# SYSTEM_BLOCK.net
KiCad netlist of a schematic drawn in Altium Designer
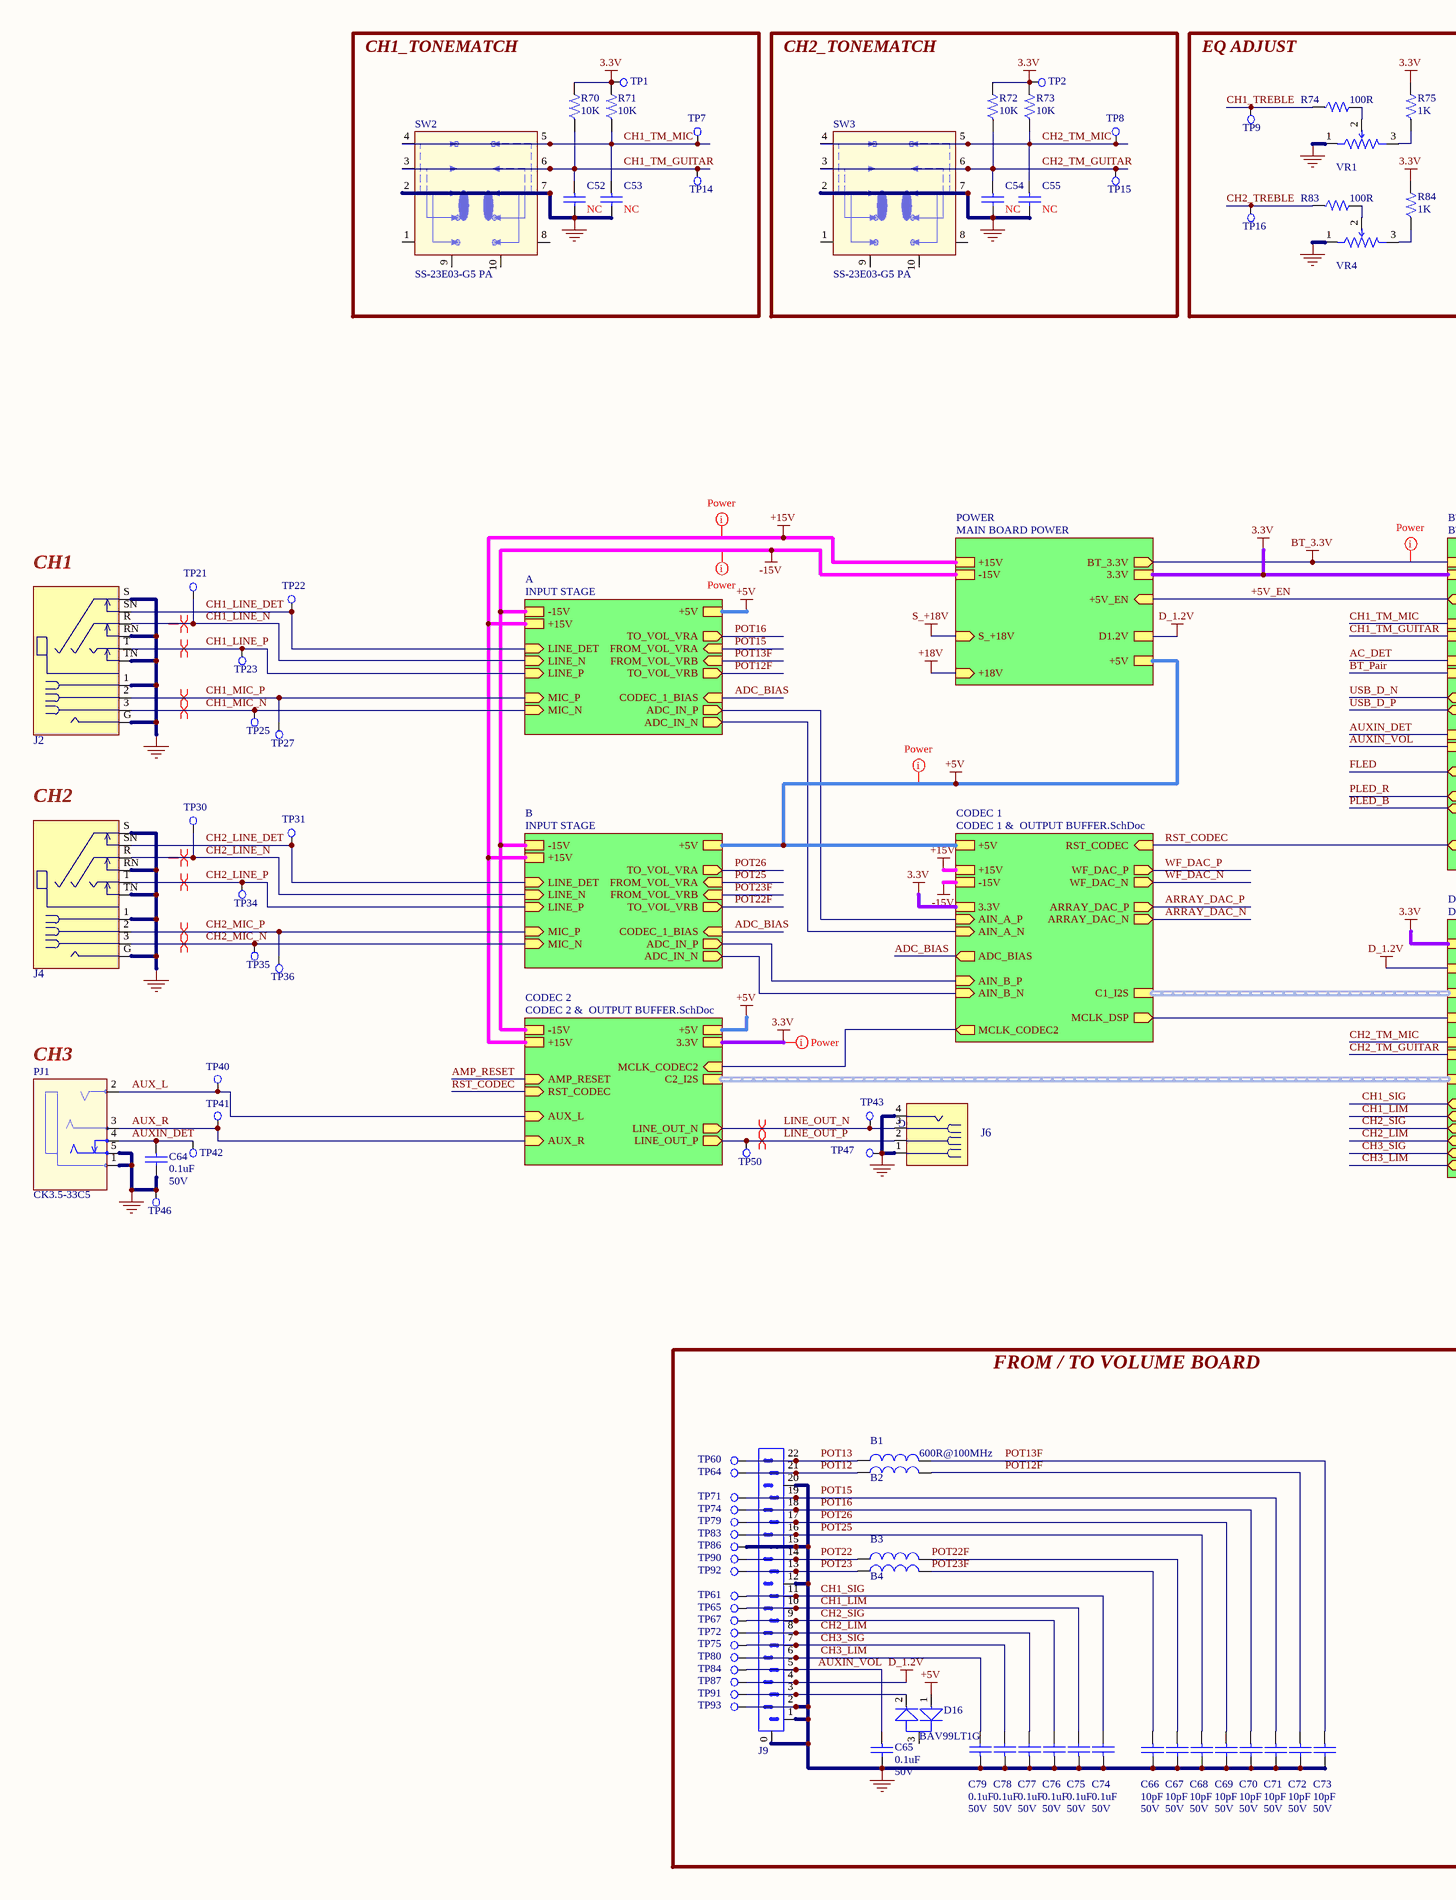
[diagram p0: SYSTEM BLOCK.SchDoc, left]
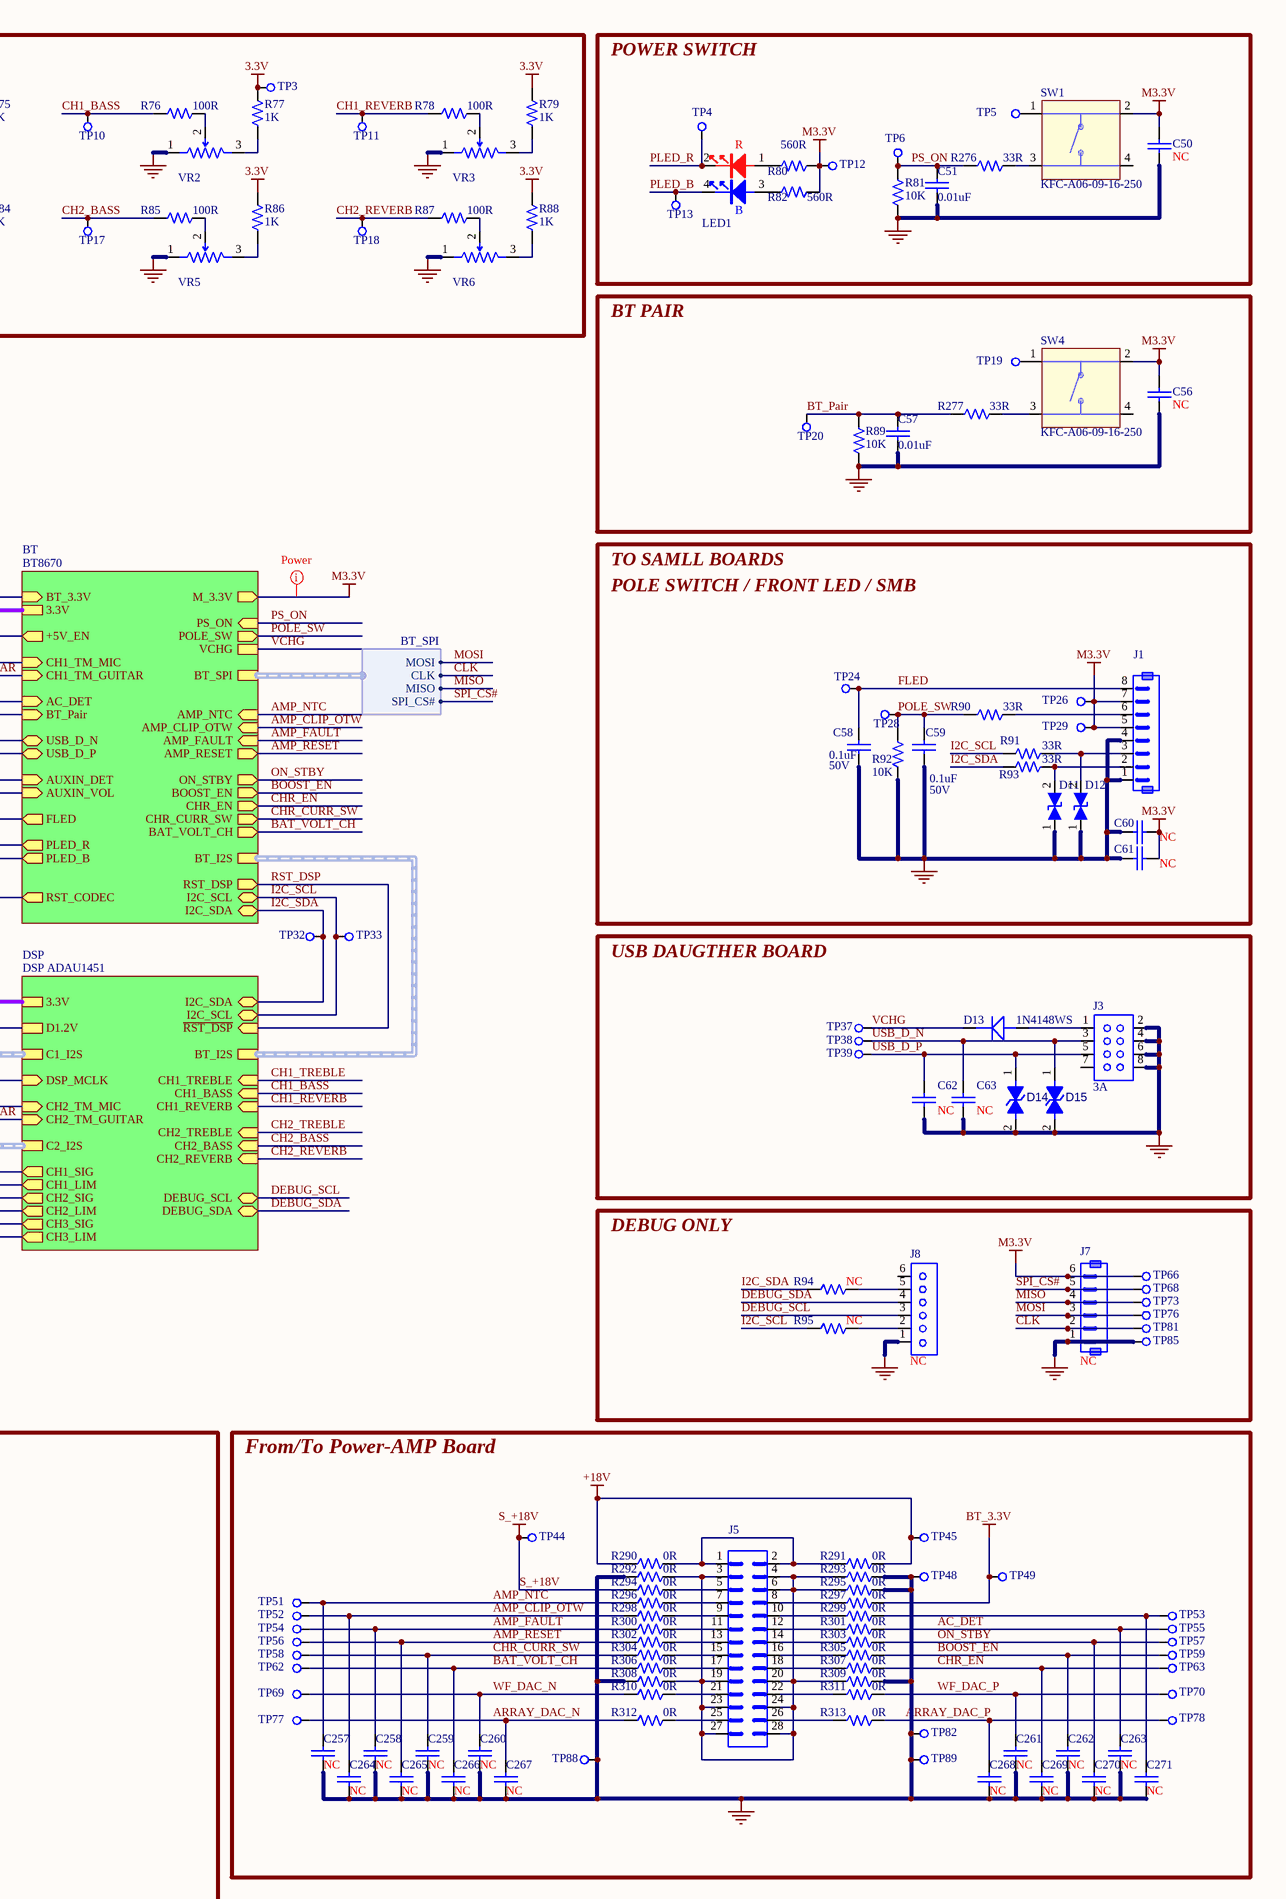
[diagram p1: SYSTEM BLOCK.SchDoc, right]

(export (version "E")
  (design (tool "Eeschema 10.0.6"))
  (components
    (comp (ref "B1")
      (value "600R@100MHz")
      (footprint "L0603-RW")
      (description "BEAD BLM18KG601SN1D 600 OHM 100M 1A L")
      (fields
        (field (name "MFG") "MURATA")
        (field (name "MFG PART") "BLM18KG601SN1D")
        (field (name "CREATE_NAME") "Nathan")
      )
      (libsource (lib "S-Inductor") (part "BEAD 0603 600R@100MHz BLM18KG601SN1D"))
    )
    (comp (ref "B2")
      (value "T710500029300")
      (footprint "L0603-RW")
      (description "BEAD BLM18KG601SN1D 600 OHM 100M 1A L")
      (fields
        (field (name "MFG") "MURATA")
        (field (name "MFG PART") "BLM18KG601SN1D")
        (field (name "CREATE_NAME") "Nathan")
      )
      (libsource (lib "S-Inductor") (part "BEAD 0603 600R@100MHz BLM18KG601SN1D"))
    )
    (comp (ref "B3")
      (value "T710500029300")
      (footprint "L0603-RW")
      (description "BEAD BLM18KG601SN1D 600 OHM 100M 1A L")
      (fields
        (field (name "MFG") "MURATA")
        (field (name "MFG PART") "BLM18KG601SN1D")
        (field (name "CREATE_NAME") "Nathan")
      )
      (libsource (lib "S-Inductor") (part "BEAD 0603 600R@100MHz BLM18KG601SN1D"))
    )
    (comp (ref "B4")
      (value "T710500029300")
      (footprint "L0603-RW")
      (description "BEAD BLM18KG601SN1D 600 OHM 100M 1A L")
      (fields
        (field (name "MFG") "MURATA")
        (field (name "MFG PART") "BLM18KG601SN1D")
        (field (name "CREATE_NAME") "Nathan")
      )
      (libsource (lib "S-Inductor") (part "BEAD 0603 600R@100MHz BLM18KG601SN1D"))
    )
    (comp (ref "C50")
      (value "NC")
      (footprint "CAPC0402-RW")
      (fields (field (name "Comment") "CAP0402 NC") (field (name "CREATE_NAME") "Tom"))
      (libsource (lib "Temporary") (part "CAP0402 NC"))
    )
    (comp (ref "C51")
      (value "0.01uF")
      (footprint "CAPC0402-RW")
      (description "CAP, CER, 0.01uF, 10%, 50V, X7R, 0402, RoHS")
      (fields
        (field (name "TOLERANCE") "10%")
        (field (name "VOLTAGE") "50V")
        (field (name "CREATE_NAME") "Evan@Deftronics")
      )
      (libsource (lib "P-Capacitors") (part "CAP0402 0.01uF 50V 10%"))
    )
    (comp (ref "C52")
      (value "NC")
      (footprint "CAPC0402-RW")
      (fields (field (name "Comment") "CAP0402 NC") (field (name "CREATE_NAME") "Tom"))
      (libsource (lib "Temporary") (part "CAP0402 NC"))
    )
    (comp (ref "C53")
      (value "NC")
      (footprint "CAPC0402-RW")
      (fields (field (name "Comment") "CAP0402 NC") (field (name "CREATE_NAME") "Tom"))
      (libsource (lib "Temporary") (part "CAP0402 NC"))
    )
    (comp (ref "C54")
      (value "NC")
      (footprint "CAPC0402-RW")
      (fields (field (name "Comment") "CAP0402 NC") (field (name "CREATE_NAME") "Tom"))
      (libsource (lib "Temporary") (part "CAP0402 NC"))
    )
    (comp (ref "C55")
      (value "NC")
      (footprint "CAPC0402-RW")
      (fields (field (name "Comment") "CAP0402 NC") (field (name "CREATE_NAME") "Tom"))
      (libsource (lib "Temporary") (part "CAP0402 NC"))
    )
    (comp (ref "C56")
      (value "NC")
      (footprint "CAPC0402-RW")
      (fields (field (name "Comment") "CAP0402 NC") (field (name "CREATE_NAME") "Tom"))
      (libsource (lib "Temporary") (part "CAP0402 NC"))
    )
    (comp (ref "C57")
      (value "0.01uF")
      (footprint "CAPC0402-RW")
      (description "CAP, CER, 0.01uF, 10%, 50V, X7R, 0402, RoHS")
      (fields
        (field (name "TOLERANCE") "10%")
        (field (name "VOLTAGE") "50V")
        (field (name "CREATE_NAME") "Evan@Deftronics")
      )
      (libsource (lib "P-Capacitors") (part "CAP0402 0.01uF 50V 10%"))
    )
    (comp (ref "C58")
      (value "0.1uF")
      (footprint "CAPC0402-RW")
      (description "CAP, CER, 0.1uF, 10%, 50V, X7R, 0402, RoHS")
      (fields
        (field (name "TOLERANCE") "10%")
        (field (name "VOLTAGE") "50V")
        (field (name "Comment") "PWL456470-1040")
        (field (name "CREATE_NAME") "TOM@Deftronics")
      )
      (libsource (lib "P-Capacitors") (part "CAP0402 0.1uF 50V 10%"))
    )
    (comp (ref "C59")
      (value "0.1uF")
      (footprint "CAPC0402-RW")
      (description "CAP, CER, 0.1uF, 10%, 50V, X7R, 0402, RoHS")
      (fields
        (field (name "TOLERANCE") "10%")
        (field (name "VOLTAGE") "50V")
        (field (name "Comment") "PWL456470-1040")
        (field (name "CREATE_NAME") "TOM@Deftronics")
      )
      (libsource (lib "P-Capacitors") (part "CAP0402 0.1uF 50V 10%"))
    )
    (comp (ref "C60")
      (value "NC")
      (footprint "CAPC0402-RW")
      (fields (field (name "Comment") "CAP0402 NC") (field (name "CREATE_NAME") "Tom"))
      (libsource (lib "Temporary") (part "CAP0402 NC"))
    )
    (comp (ref "C61")
      (value "NC")
      (footprint "CAPC0402-RW")
      (fields (field (name "Comment") "CAP0402 NC") (field (name "CREATE_NAME") "Tom"))
      (libsource (lib "Temporary") (part "CAP0402 NC"))
    )
    (comp (ref "C62")
      (value "NC")
      (footprint "CAPC0402-RW")
      (fields (field (name "Comment") "CAP0402 NC") (field (name "CREATE_NAME") "Tom"))
      (libsource (lib "Temporary") (part "CAP0402 NC"))
    )
    (comp (ref "C63")
      (value "NC")
      (footprint "CAPC0402-RW")
      (fields (field (name "Comment") "CAP0402 NC") (field (name "CREATE_NAME") "Tom"))
      (libsource (lib "Temporary") (part "CAP0402 NC"))
    )
    (comp (ref "C64")
      (value "0.1uF")
      (footprint "CAPC0402-RW")
      (description "CAP, CER, 0.1uF, 10%, 50V, X7R, 0402, RoHS")
      (fields
        (field (name "TOLERANCE") "10%")
        (field (name "VOLTAGE") "50V")
        (field (name "Comment") "PWL456470-1040")
        (field (name "CREATE_NAME") "TOM@Deftronics")
      )
      (libsource (lib "P-Capacitors") (part "CAP0402 0.1uF 50V 10%"))
    )
    (comp (ref "C65")
      (value "0.1uF")
      (footprint "CAPC0402-RW")
      (description "CAP, CER, 0.1uF, 10%, 50V, X7R, 0402, RoHS")
      (fields
        (field (name "TOLERANCE") "10%")
        (field (name "VOLTAGE") "50V")
        (field (name "Comment") "PWL456470-1040")
        (field (name "CREATE_NAME") "TOM@Deftronics")
      )
      (libsource (lib "P-Capacitors") (part "CAP0402 0.1uF 50V 10%"))
    )
    (comp (ref "C66")
      (value "10pF")
      (footprint "CAPC0402-RW")
      (description "CHIP CAP 5% 50V 0402 NPO 10pF")
      (fields
        (field (name "TOLERANCE") "5%")
        (field (name "VOLTAGE") "50V")
        (field (name "Comment") "PWL410371-1000")
        (field (name "CREATE_NAME") "TOM@Deftronics")
      )
      (libsource (lib "P-Capacitors") (part "CAP0402 10pF 50V 5%"))
    )
    (comp (ref "C67")
      (value "10pF")
      (footprint "CAPC0402-RW")
      (description "CHIP CAP 5% 50V 0402 NPO 10pF")
      (fields
        (field (name "TOLERANCE") "5%")
        (field (name "VOLTAGE") "50V")
        (field (name "Comment") "PWL410371-1000")
        (field (name "CREATE_NAME") "TOM@Deftronics")
      )
      (libsource (lib "P-Capacitors") (part "CAP0402 10pF 50V 5%"))
    )
    (comp (ref "C68")
      (value "10pF")
      (footprint "CAPC0402-RW")
      (description "CHIP CAP 5% 50V 0402 NPO 10pF")
      (fields
        (field (name "TOLERANCE") "5%")
        (field (name "VOLTAGE") "50V")
        (field (name "Comment") "PWL410371-1000")
        (field (name "CREATE_NAME") "TOM@Deftronics")
      )
      (libsource (lib "P-Capacitors") (part "CAP0402 10pF 50V 5%"))
    )
    (comp (ref "C69")
      (value "10pF")
      (footprint "CAPC0402-RW")
      (description "CHIP CAP 5% 50V 0402 NPO 10pF")
      (fields
        (field (name "TOLERANCE") "5%")
        (field (name "VOLTAGE") "50V")
        (field (name "Comment") "PWL410371-1000")
        (field (name "CREATE_NAME") "TOM@Deftronics")
      )
      (libsource (lib "P-Capacitors") (part "CAP0402 10pF 50V 5%"))
    )
    (comp (ref "C70")
      (value "10pF")
      (footprint "CAPC0402-RW")
      (description "CHIP CAP 5% 50V 0402 NPO 10pF")
      (fields
        (field (name "TOLERANCE") "5%")
        (field (name "VOLTAGE") "50V")
        (field (name "Comment") "PWL410371-1000")
        (field (name "CREATE_NAME") "TOM@Deftronics")
      )
      (libsource (lib "P-Capacitors") (part "CAP0402 10pF 50V 5%"))
    )
    (comp (ref "C71")
      (value "10pF")
      (footprint "CAPC0402-RW")
      (description "CHIP CAP 5% 50V 0402 NPO 10pF")
      (fields
        (field (name "TOLERANCE") "5%")
        (field (name "VOLTAGE") "50V")
        (field (name "Comment") "PWL410371-1000")
        (field (name "CREATE_NAME") "TOM@Deftronics")
      )
      (libsource (lib "P-Capacitors") (part "CAP0402 10pF 50V 5%"))
    )
    (comp (ref "C72")
      (value "10pF")
      (footprint "CAPC0402-RW")
      (description "CHIP CAP 5% 50V 0402 NPO 10pF")
      (fields
        (field (name "TOLERANCE") "5%")
        (field (name "VOLTAGE") "50V")
        (field (name "Comment") "PWL410371-1000")
        (field (name "CREATE_NAME") "TOM@Deftronics")
      )
      (libsource (lib "P-Capacitors") (part "CAP0402 10pF 50V 5%"))
    )
    (comp (ref "C73")
      (value "10pF")
      (footprint "CAPC0402-RW")
      (description "CHIP CAP 5% 50V 0402 NPO 10pF")
      (fields
        (field (name "TOLERANCE") "5%")
        (field (name "VOLTAGE") "50V")
        (field (name "Comment") "PWL410371-1000")
        (field (name "CREATE_NAME") "TOM@Deftronics")
      )
      (libsource (lib "P-Capacitors") (part "CAP0402 10pF 50V 5%"))
    )
    (comp (ref "C74")
      (value "0.1uF")
      (footprint "CAPC0402-RW")
      (description "CAP, CER, 0.1uF, 10%, 50V, X7R, 0402, RoHS")
      (fields
        (field (name "TOLERANCE") "10%")
        (field (name "VOLTAGE") "50V")
        (field (name "Comment") "PWL456470-1040")
        (field (name "CREATE_NAME") "TOM@Deftronics")
      )
      (libsource (lib "P-Capacitors") (part "CAP0402 0.1uF 50V 10%"))
    )
    (comp (ref "C75")
      (value "0.1uF")
      (footprint "CAPC0402-RW")
      (description "CAP, CER, 0.1uF, 10%, 50V, X7R, 0402, RoHS")
      (fields
        (field (name "TOLERANCE") "10%")
        (field (name "VOLTAGE") "50V")
        (field (name "Comment") "PWL456470-1040")
        (field (name "CREATE_NAME") "TOM@Deftronics")
      )
      (libsource (lib "P-Capacitors") (part "CAP0402 0.1uF 50V 10%"))
    )
    (comp (ref "C76")
      (value "0.1uF")
      (footprint "CAPC0402-RW")
      (description "CAP, CER, 0.1uF, 10%, 50V, X7R, 0402, RoHS")
      (fields
        (field (name "TOLERANCE") "10%")
        (field (name "VOLTAGE") "50V")
        (field (name "Comment") "PWL456470-1040")
        (field (name "CREATE_NAME") "TOM@Deftronics")
      )
      (libsource (lib "P-Capacitors") (part "CAP0402 0.1uF 50V 10%"))
    )
    (comp (ref "C77")
      (value "0.1uF")
      (footprint "CAPC0402-RW")
      (description "CAP, CER, 0.1uF, 10%, 50V, X7R, 0402, RoHS")
      (fields
        (field (name "TOLERANCE") "10%")
        (field (name "VOLTAGE") "50V")
        (field (name "Comment") "PWL456470-1040")
        (field (name "CREATE_NAME") "TOM@Deftronics")
      )
      (libsource (lib "P-Capacitors") (part "CAP0402 0.1uF 50V 10%"))
    )
    (comp (ref "C78")
      (value "0.1uF")
      (footprint "CAPC0402-RW")
      (description "CAP, CER, 0.1uF, 10%, 50V, X7R, 0402, RoHS")
      (fields
        (field (name "TOLERANCE") "10%")
        (field (name "VOLTAGE") "50V")
        (field (name "Comment") "PWL456470-1040")
        (field (name "CREATE_NAME") "TOM@Deftronics")
      )
      (libsource (lib "P-Capacitors") (part "CAP0402 0.1uF 50V 10%"))
    )
    (comp (ref "C79")
      (value "0.1uF")
      (footprint "CAPC0402-RW")
      (description "CAP, CER, 0.1uF, 10%, 50V, X7R, 0402, RoHS")
      (fields
        (field (name "TOLERANCE") "10%")
        (field (name "VOLTAGE") "50V")
        (field (name "Comment") "PWL456470-1040")
        (field (name "CREATE_NAME") "TOM@Deftronics")
      )
      (libsource (lib "P-Capacitors") (part "CAP0402 0.1uF 50V 10%"))
    )
    (comp (ref "C257")
      (value "NC")
      (footprint "CAPC0603-RW")
      (fields (field (name "Comment") "CAP0603 NC") (field (name "CREATE_NAME") "Tom"))
      (libsource (lib "Temporary") (part "CAP0603 NC"))
    )
    (comp (ref "C258")
      (value "NC")
      (footprint "CAPC0603-RW")
      (fields (field (name "Comment") "CAP0603 NC") (field (name "CREATE_NAME") "Tom"))
      (libsource (lib "Temporary") (part "CAP0603 NC"))
    )
    (comp (ref "C259")
      (value "NC")
      (footprint "CAPC0603-RW")
      (fields (field (name "Comment") "CAP0603 NC") (field (name "CREATE_NAME") "Tom"))
      (libsource (lib "Temporary") (part "CAP0603 NC"))
    )
    (comp (ref "C260")
      (value "NC")
      (footprint "CAPC0603-RW")
      (fields (field (name "Comment") "CAP0603 NC") (field (name "CREATE_NAME") "Tom"))
      (libsource (lib "Temporary") (part "CAP0603 NC"))
    )
    (comp (ref "C261")
      (value "NC")
      (footprint "CAPC0603-RW")
      (fields (field (name "Comment") "CAP0603 NC") (field (name "CREATE_NAME") "Tom"))
      (libsource (lib "Temporary") (part "CAP0603 NC"))
    )
    (comp (ref "C262")
      (value "NC")
      (footprint "CAPC0603-RW")
      (fields (field (name "Comment") "CAP0603 NC") (field (name "CREATE_NAME") "Tom"))
      (libsource (lib "Temporary") (part "CAP0603 NC"))
    )
    (comp (ref "C263")
      (value "NC")
      (footprint "CAPC0603-RW")
      (fields (field (name "Comment") "CAP0603 NC") (field (name "CREATE_NAME") "Tom"))
      (libsource (lib "Temporary") (part "CAP0603 NC"))
    )
    (comp (ref "C264")
      (value "NC")
      (footprint "CAPC0603-RW")
      (fields (field (name "Comment") "CAP0603 NC") (field (name "CREATE_NAME") "Tom"))
      (libsource (lib "Temporary") (part "CAP0603 NC"))
    )
    (comp (ref "C265")
      (value "NC")
      (footprint "CAPC0603-RW")
      (fields (field (name "Comment") "CAP0603 NC") (field (name "CREATE_NAME") "Tom"))
      (libsource (lib "Temporary") (part "CAP0603 NC"))
    )
    (comp (ref "C266")
      (value "NC")
      (footprint "CAPC0603-RW")
      (fields (field (name "Comment") "CAP0603 NC") (field (name "CREATE_NAME") "Tom"))
      (libsource (lib "Temporary") (part "CAP0603 NC"))
    )
    (comp (ref "C267")
      (value "NC")
      (footprint "CAPC0603-RW")
      (fields (field (name "Comment") "CAP0603 NC") (field (name "CREATE_NAME") "Tom"))
      (libsource (lib "Temporary") (part "CAP0603 NC"))
    )
    (comp (ref "C268")
      (value "NC")
      (footprint "CAPC0603-RW")
      (fields (field (name "Comment") "CAP0603 NC") (field (name "CREATE_NAME") "Tom"))
      (libsource (lib "Temporary") (part "CAP0603 NC"))
    )
    (comp (ref "C269")
      (value "NC")
      (footprint "CAPC0603-RW")
      (fields (field (name "Comment") "CAP0603 NC") (field (name "CREATE_NAME") "Tom"))
      (libsource (lib "Temporary") (part "CAP0603 NC"))
    )
    (comp (ref "C270")
      (value "NC")
      (footprint "CAPC0603-RW")
      (fields (field (name "Comment") "CAP0603 NC") (field (name "CREATE_NAME") "Tom"))
      (libsource (lib "Temporary") (part "CAP0603 NC"))
    )
    (comp (ref "C271")
      (value "NC")
      (footprint "CAPC0603-RW")
      (fields (field (name "Comment") "CAP0603 NC") (field (name "CREATE_NAME") "Tom"))
      (libsource (lib "Temporary") (part "CAP0603 NC"))
    )
    (comp (ref "D11")
      (value "T710500020400")
      (footprint "VAR-0402")
      (description "VR AVRM1005C120MTAAB TDK K")
      (fields
        (field (name "MFG") "TDK")
        (field (name "MFG PART") "AVRM1005C120MTAAB")
        (field (name "CREAT NAME") "QCD")
      )
      (libsource (lib "R-Semiconductors") (part "AVRM1005C120MTAAB"))
    )
    (comp (ref "D12")
      (value "T710500020400")
      (footprint "VAR-0402")
      (description "VR AVRM1005C120MTAAB TDK K")
      (fields
        (field (name "MFG") "TDK")
        (field (name "MFG PART") "AVRM1005C120MTAAB")
        (field (name "CREAT NAME") "QCD")
      )
      (libsource (lib "R-Semiconductors") (part "AVRM1005C120MTAAB"))
    )
    (comp (ref "D13")
      (value "RCD114148-0020")
      (footprint "SOD-323")
      (description "DIODE SW 1N4148 VF=0.7V SOD-323")
      (fields
        (field (name "MFG") "TW SEMICONDUCTOR")
        (field (name "VOLTAGE") "100V")
        (field (name "MFG PART") "1N4148WS")
      )
      (libsource (lib "R-Semiconductors") (part "1N4148WS"))
    )
    (comp (ref "D14")
      (value "T593000120100")
      (footprint "SOD882-ESD")
      (description "TVS 5V L06ESDU5V0CE SMD LITEON L")
      (fields
        (field (name "MFG") "LITEON")
        (field (name "MFG PART") "L06ESDU5V0CE2")
        (field (name "CREATE_NAME") "Tom")
      )
      (libsource (lib "R-Semiconductors") (part "L06ESDU5V0CE2"))
    )
    (comp (ref "D15")
      (value "T593000120100")
      (footprint "SOD882-ESD")
      (description "TVS 5V L06ESDU5V0CE SMD LITEON L")
      (fields
        (field (name "MFG") "LITEON")
        (field (name "MFG PART") "L06ESDU5V0CE2")
        (field (name "CREATE_NAME") "Tom")
      )
      (libsource (lib "R-Semiconductors") (part "L06ESDU5V0CE2"))
    )
    (comp (ref "D16")
      (value "RCD100099-0010")
      (footprint "SOT23-132-RW")
      (description "SWITC 70V 215MA BAV99LT1G ON SE G")
      (fields
        (field (name "MFG") "ON SEMI")
        (field (name "MFG PART") "BAV99LT1G")
        (field (name "VOLTAGE") "100V")
      )
      (libsource (lib "R-Semiconductors") (part "BAV99LT1G"))
    )
    (comp (ref "J1")
      (value "T690300162000")
      (footprint "CONN 8P PH=1.5mm ST SMT_ZH-8AT-JK")
      (description "SMT CONNECTOR 8PIN P:1.5MM 90 K")
      (fields
        (field (name "MFG") "金佳")
        (field (name "MFG PART") "ZH-8AT-JK")
        (field (name "CREATE_NAME") "Nathan")
      )
      (libsource (lib "C-Connector") (part "CONN 8P PH=1.5mm ST SMT_ZH-8AT-JK"))
    )
    (comp (ref "J2")
      (value "T710200010000")
      (footprint "CONN XLR COMBO RCJ9FI-V-0")
      (description "COMBO JACK RCJ9FI-V-0 REAN K")
      (fields
        (field (name "MFG") "REAN")
        (field (name "MFG PART") "RCJ9FI-V-0")
        (field (name "CREATE_NAME") "Nathan")
      )
      (libsource (lib "C-Connector") (part "CONN XLR COMBO RCJ9FI-V-0"))
    )
    (comp (ref "J3")
      (value "USB DAUGHTER BOARD")
      (footprint "USB DAUGHTER BOARD")
      (fields (field (name "CURRENT") "3A"))
      (libsource (lib "Yetta_Lib") (part "USB DAUGHTER BOARD"))
    )
    (comp (ref "J4")
      (value "T710200010000")
      (footprint "CONN XLR COMBO RCJ9FI-V-0")
      (description "COMBO JACK RCJ9FI-V-0 REAN K")
      (fields
        (field (name "MFG") "REAN")
        (field (name "MFG PART") "RCJ9FI-V-0")
        (field (name "CREATE_NAME") "Nathan")
      )
      (libsource (lib "C-Connector") (part "CONN XLR COMBO RCJ9FI-V-0"))
    )
    (comp (ref "J5")
      (value "T690300164900")
      (footprint "HOUSING 28P 2X14 PH=2.54mm ST SMT 2.54Y-2X14SW-10.6R")
      (description "CONNECTOR 2X14PIN P:2.54 90 H:10.6 K")
      (fields
        (field (name "MFG") "JIN JIA")
        (field (name "MFG PART") "2.54Y-2X14SW-10.6R")
        (field (name "CREATE_NAME") "Nathan")
      )
      (libsource (lib "C-Connector") (part "HOUSING 28P 2X14 PH=2.54mm ST SMT 2.54Y-2X14SW-10.6R"))
    )
    (comp (ref "J6")
      (value "T710200009900")
      (footprint "CONN XLR 3P NC3MAV-0")
      (description "3 POLE MALE XLR RECEPTACLE K")
      (fields
        (field (name "MFG") "NEUTRIK")
        (field (name "MFG PART") "NC3MAV-0")
        (field (name "CREATE_NAME") "Nathan")
      )
      (libsource (lib "C-Connector") (part "CONN XLR 3P NC3MAV-0"))
    )
    (comp (ref "J7")
      (value "NC")
      (footprint "CONN 6P PH=1.5mm ST SMT ZH-6AT-JK")
      (description "CHIP CONNECTOR 6PIN P:1.5MM 90 G")
      (fields
        (field (name "MFG") "金佳")
        (field (name "MFG PART") "ZH-6AT-JK")
        (field (name "CREATE_NAME") "Nathan")
      )
      (libsource (lib "C-Connector") (part "CONN 6P PH=1.5mm ST SMT ZH-6AT-JK"))
    )
    (comp (ref "J8")
      (value "NC")
      (footprint "CONN 6P PH=2.0MM ST_PH-6A-CS")
      (description "CONNECTOR 6IN 2.0MM DIP 180 K")
      (fields
        (field (name "MFG") "金佳电子")
        (field (name "MFG PART") "PH-6A-CS")
        (field (name "CREATE_NAME") "Nathan")
      )
      (libsource (lib "C-Connector") (part "CONN 6P PH=2.0MM ST_PH-6A-CS"))
    )
    (comp (ref "J9")
      (value "T690300162900")
      (footprint "CONN FFC 22P PH=0.5MM SMT ST 0.5S-4-22PTFAR")
      (description "FFC CONNECTOR 22P 0.5MM GOLD PLATED L")
      (fields
        (field (name "MFG") "金佳")
        (field (name "MFG PART") "0.5S-4-22PTFAR")
        (field (name "CREATE_NAME") "Nathan")
      )
      (libsource (lib "C-Connector") (part "CONN FFC 22P 2X11 PH=0.5MM SMT ST 0.5S-4-22PTFAR"))
    )
    (comp (ref "LED1")
      (value "KCD260004-0010")
      (footprint "SMTLED2.0*1.25-RGB")
      (description "SMD LED 2.0x1.25mm  MS-PTB2012CURSBAC   RED/BLUE")
      (fields
        (field (name "MFG PART") "MS-PTB2012CURSGAC  RED/BLUE")
        (field (name "MFG") "MASON")
        (field (name "CREATE_NAME") "Evan@Deftronics")
      )
      (libsource (lib "K-LED-FUSE") (part "MS-PTB2012CURSGAC_RED/BLUE"))
    )
    (comp (ref "PJ1")
      (value "T710200010500")
      (footprint "Phone Jack CK3.5-33C5")
      (description "EARPHONE JACK K")
      (fields
        (field (name "MFG") "JINJIA")
        (field (name "MFG PART") "CK3.5-33C5")
        (field (name "CREATE_NAME") "Nathan")
      )
      (libsource (lib "C-Connector") (part "PHONE JACK 3.5mm CK3.5-33C5"))
    )
    (comp (ref "R70")
      (value "10K")
      (footprint "0402-RW")
      (description "CHIP RES 10K OHM 1/16W 1% 0402")
      (fields (field (name "MFG") "WALSIN") (field (name "Comment") "QCF161240-1002"))
      (libsource (lib "Q-Resistors") (part "RES0402 1/16W 1% 10K OHM"))
    )
    (comp (ref "R71")
      (value "10K")
      (footprint "0402-RW")
      (description "CHIP RES 10K OHM 1/16W 1% 0402")
      (fields (field (name "MFG") "WALSIN") (field (name "Comment") "QCF161240-1002"))
      (libsource (lib "Q-Resistors") (part "RES0402 1/16W 1% 10K OHM"))
    )
    (comp (ref "R72")
      (value "10K")
      (footprint "0402-RW")
      (description "CHIP RES 10K OHM 1/16W 1% 0402")
      (fields (field (name "MFG") "WALSIN") (field (name "Comment") "QCF161240-1002"))
      (libsource (lib "Q-Resistors") (part "RES0402 1/16W 1% 10K OHM"))
    )
    (comp (ref "R73")
      (value "10K")
      (footprint "0402-RW")
      (description "CHIP RES 10K OHM 1/16W 1% 0402")
      (fields (field (name "MFG") "WALSIN") (field (name "Comment") "QCF161240-1002"))
      (libsource (lib "Q-Resistors") (part "RES0402 1/16W 1% 10K OHM"))
    )
    (comp (ref "R74")
      (value "100R")
      (footprint "0402-RW")
      (description "CHIP RES 100 OHM 1/16W 1% 0402")
      (fields (field (name "MFG") "WALSIN") (field (name "Comment") "QCF161240-1000"))
      (libsource (lib "Q-Resistors") (part "RES0402 1/16W 1% 100 OHM"))
    )
    (comp (ref "R75")
      (value "1K")
      (footprint "0402-RW")
      (description "CHIP RES 1K OHM 1/16W 1% 0402")
      (fields (field (name "MFG") "WALSIN") (field (name "Comment") "QCF161240-1001"))
      (libsource (lib "Q-Resistors") (part "RES0402 1/16W 1% 1K OHM"))
    )
    (comp (ref "R76")
      (value "100R")
      (footprint "0402-RW")
      (description "CHIP RES 100 OHM 1/16W 1% 0402")
      (fields (field (name "MFG") "WALSIN") (field (name "Comment") "QCF161240-1000"))
      (libsource (lib "Q-Resistors") (part "RES0402 1/16W 1% 100 OHM"))
    )
    (comp (ref "R77")
      (value "1K")
      (footprint "0402-RW")
      (description "CHIP RES 1K OHM 1/16W 1% 0402")
      (fields (field (name "MFG") "WALSIN") (field (name "Comment") "QCF161240-1001"))
      (libsource (lib "Q-Resistors") (part "RES0402 1/16W 1% 1K OHM"))
    )
    (comp (ref "R78")
      (value "100R")
      (footprint "0402-RW")
      (description "CHIP RES 100 OHM 1/16W 1% 0402")
      (fields (field (name "MFG") "WALSIN") (field (name "Comment") "QCF161240-1000"))
      (libsource (lib "Q-Resistors") (part "RES0402 1/16W 1% 100 OHM"))
    )
    (comp (ref "R79")
      (value "1K")
      (footprint "0402-RW")
      (description "CHIP RES 1K OHM 1/16W 1% 0402")
      (fields (field (name "MFG") "WALSIN") (field (name "Comment") "QCF161240-1001"))
      (libsource (lib "Q-Resistors") (part "RES0402 1/16W 1% 1K OHM"))
    )
    (comp (ref "R80")
      (value "560R")
      (footprint "0603-RW")
      (description "GP CHIP RES. 560 OHM 1/10W 1% 0603")
      (fields (field (name "Comment") "QCF011030-5600"))
      (libsource (lib "Q-Resistors") (part "RES0603 1/10W 1% 560 OHM"))
    )
    (comp (ref "R81")
      (value "10K")
      (footprint "0402-RW")
      (description "CHIP RES 10K OHM 1/16W 1% 0402")
      (fields (field (name "MFG") "WALSIN") (field (name "Comment") "QCF161240-1002"))
      (libsource (lib "Q-Resistors") (part "RES0402 1/16W 1% 10K OHM"))
    )
    (comp (ref "R82")
      (value "560R")
      (footprint "0603-RW")
      (description "GP CHIP RES. 560 OHM 1/10W 1% 0603")
      (fields (field (name "Comment") "QCF011030-5600"))
      (libsource (lib "Q-Resistors") (part "RES0603 1/10W 1% 560 OHM"))
    )
    (comp (ref "R83")
      (value "100R")
      (footprint "0402-RW")
      (description "CHIP RES 100 OHM 1/16W 1% 0402")
      (fields (field (name "MFG") "WALSIN") (field (name "Comment") "QCF161240-1000"))
      (libsource (lib "Q-Resistors") (part "RES0402 1/16W 1% 100 OHM"))
    )
    (comp (ref "R84")
      (value "1K")
      (footprint "0402-RW")
      (description "CHIP RES 1K OHM 1/16W 1% 0402")
      (fields (field (name "MFG") "WALSIN") (field (name "Comment") "QCF161240-1001"))
      (libsource (lib "Q-Resistors") (part "RES0402 1/16W 1% 1K OHM"))
    )
    (comp (ref "R85")
      (value "100R")
      (footprint "0402-RW")
      (description "CHIP RES 100 OHM 1/16W 1% 0402")
      (fields (field (name "MFG") "WALSIN") (field (name "Comment") "QCF161240-1000"))
      (libsource (lib "Q-Resistors") (part "RES0402 1/16W 1% 100 OHM"))
    )
    (comp (ref "R86")
      (value "1K")
      (footprint "0402-RW")
      (description "CHIP RES 1K OHM 1/16W 1% 0402")
      (fields (field (name "MFG") "WALSIN") (field (name "Comment") "QCF161240-1001"))
      (libsource (lib "Q-Resistors") (part "RES0402 1/16W 1% 1K OHM"))
    )
    (comp (ref "R87")
      (value "100R")
      (footprint "0402-RW")
      (description "CHIP RES 100 OHM 1/16W 1% 0402")
      (fields (field (name "MFG") "WALSIN") (field (name "Comment") "QCF161240-1000"))
      (libsource (lib "Q-Resistors") (part "RES0402 1/16W 1% 100 OHM"))
    )
    (comp (ref "R88")
      (value "1K")
      (footprint "0402-RW")
      (description "CHIP RES 1K OHM 1/16W 1% 0402")
      (fields (field (name "MFG") "WALSIN") (field (name "Comment") "QCF161240-1001"))
      (libsource (lib "Q-Resistors") (part "RES0402 1/16W 1% 1K OHM"))
    )
    (comp (ref "R89")
      (value "10K")
      (footprint "0402-RW")
      (description "CHIP RES 10K OHM 1/16W 1% 0402")
      (fields (field (name "MFG") "WALSIN") (field (name "Comment") "QCF161240-1002"))
      (libsource (lib "Q-Resistors") (part "RES0402 1/16W 1% 10K OHM"))
    )
    (comp (ref "R90")
      (value "33R")
      (footprint "0402-RW")
      (description "CHIP RES 33 OHM 1/16W 1% 0402")
      (fields (field (name "POWER") "1/16W") (field (name "MFG") "WALSIN"))
      (libsource (lib "Q-Resistors") (part "RES0402 1/16W 1% 33 OHM"))
    )
    (comp (ref "R91")
      (value "33R")
      (footprint "0402-RW")
      (description "CHIP RES 33 OHM 1/16W 1% 0402")
      (fields (field (name "POWER") "1/16W") (field (name "MFG") "WALSIN"))
      (libsource (lib "Q-Resistors") (part "RES0402 1/16W 1% 33 OHM"))
    )
    (comp (ref "R92")
      (value "10K")
      (footprint "0402-RW")
      (description "CHIP RES 10K OHM 1/16W 1% 0402")
      (fields (field (name "POWER") "1/16W") (field (name "MFG") "WALSIN"))
      (libsource (lib "Q-Resistors") (part "RES0402 1/16W 1% 10K OHM"))
    )
    (comp (ref "R93")
      (value "33R")
      (footprint "0402-RW")
      (description "CHIP RES 33 OHM 1/16W 1% 0402")
      (fields (field (name "POWER") "1/16W") (field (name "MFG") "WALSIN"))
      (libsource (lib "Q-Resistors") (part "RES0402 1/16W 1% 33 OHM"))
    )
    (comp (ref "R94")
      (value "NC")
      (footprint "0603-RW")
      (fields (field (name "Comment") "RES0603 NC") (field (name "CREATE_NAME") "Tom"))
      (libsource (lib "Temporary") (part "RES0603 NC"))
    )
    (comp (ref "R95")
      (value "NC")
      (footprint "0603-RW")
      (fields (field (name "Comment") "RES0603 NC") (field (name "CREATE_NAME") "Tom"))
      (libsource (lib "Temporary") (part "RES0603 NC"))
    )
    (comp (ref "R276")
      (value "33R")
      (footprint "0402-RW")
      (description "CHIP RES 33 OHM 1/16W 1% 0402")
      (fields (field (name "POWER") "1/16W") (field (name "MFG") "WALSIN"))
      (libsource (lib "Q-Resistors") (part "RES0402 1/16W 1% 33 OHM"))
    )
    (comp (ref "R277")
      (value "33R")
      (footprint "0402-RW")
      (description "CHIP RES 33 OHM 1/16W 1% 0402")
      (fields (field (name "POWER") "1/16W") (field (name "MFG") "WALSIN"))
      (libsource (lib "Q-Resistors") (part "RES0402 1/16W 1% 33 OHM"))
    )
    (comp (ref "R290")
      (value "0R")
      (footprint "0603-RW")
      (description "GP CHIP RES. 0 OHM 1/10W 5% 0603")
      (fields (field (name "POWER") "1/10W") (field (name "Comment") "QCF015030-0000"))
      (libsource (lib "Q-Resistors") (part "RES0603 1/10W 5% 0 OHM"))
    )
    (comp (ref "R291")
      (value "0R")
      (footprint "0603-RW")
      (description "GP CHIP RES. 0 OHM 1/10W 5% 0603")
      (fields (field (name "POWER") "1/10W") (field (name "Comment") "QCF015030-0000"))
      (libsource (lib "Q-Resistors") (part "RES0603 1/10W 5% 0 OHM"))
    )
    (comp (ref "R292")
      (value "0R")
      (footprint "0603-RW")
      (description "GP CHIP RES. 0 OHM 1/10W 5% 0603")
      (fields (field (name "POWER") "1/10W") (field (name "Comment") "QCF015030-0000"))
      (libsource (lib "Q-Resistors") (part "RES0603 1/10W 5% 0 OHM"))
    )
    (comp (ref "R293")
      (value "0R")
      (footprint "0603-RW")
      (description "GP CHIP RES. 0 OHM 1/10W 5% 0603")
      (fields (field (name "POWER") "1/10W") (field (name "Comment") "QCF015030-0000"))
      (libsource (lib "Q-Resistors") (part "RES0603 1/10W 5% 0 OHM"))
    )
    (comp (ref "R294")
      (value "0R")
      (footprint "0603-RW")
      (description "GP CHIP RES. 0 OHM 1/10W 5% 0603")
      (fields (field (name "POWER") "1/10W") (field (name "Comment") "QCF015030-0000"))
      (libsource (lib "Q-Resistors") (part "RES0603 1/10W 5% 0 OHM"))
    )
    (comp (ref "R295")
      (value "0R")
      (footprint "0603-RW")
      (description "GP CHIP RES. 0 OHM 1/10W 5% 0603")
      (fields (field (name "POWER") "1/10W") (field (name "Comment") "QCF015030-0000"))
      (libsource (lib "Q-Resistors") (part "RES0603 1/10W 5% 0 OHM"))
    )
    (comp (ref "R296")
      (value "0R")
      (footprint "0603-RW")
      (description "GP CHIP RES. 0 OHM 1/10W 5% 0603")
      (fields (field (name "POWER") "1/10W") (field (name "Comment") "QCF015030-0000"))
      (libsource (lib "Q-Resistors") (part "RES0603 1/10W 5% 0 OHM"))
    )
    (comp (ref "R297")
      (value "0R")
      (footprint "0603-RW")
      (description "GP CHIP RES. 0 OHM 1/10W 5% 0603")
      (fields (field (name "POWER") "1/10W") (field (name "Comment") "QCF015030-0000"))
      (libsource (lib "Q-Resistors") (part "RES0603 1/10W 5% 0 OHM"))
    )
    (comp (ref "R298")
      (value "0R")
      (footprint "0603-RW")
      (description "GP CHIP RES. 0 OHM 1/10W 5% 0603")
      (fields (field (name "POWER") "1/10W") (field (name "Comment") "QCF015030-0000"))
      (libsource (lib "Q-Resistors") (part "RES0603 1/10W 5% 0 OHM"))
    )
    (comp (ref "R299")
      (value "0R")
      (footprint "0603-RW")
      (description "GP CHIP RES. 0 OHM 1/10W 5% 0603")
      (fields (field (name "POWER") "1/10W") (field (name "Comment") "QCF015030-0000"))
      (libsource (lib "Q-Resistors") (part "RES0603 1/10W 5% 0 OHM"))
    )
    (comp (ref "R300")
      (value "0R")
      (footprint "0603-RW")
      (description "GP CHIP RES. 0 OHM 1/10W 5% 0603")
      (fields (field (name "POWER") "1/10W") (field (name "Comment") "QCF015030-0000"))
      (libsource (lib "Q-Resistors") (part "RES0603 1/10W 5% 0 OHM"))
    )
    (comp (ref "R301")
      (value "0R")
      (footprint "0603-RW")
      (description "GP CHIP RES. 0 OHM 1/10W 5% 0603")
      (fields (field (name "POWER") "1/10W") (field (name "Comment") "QCF015030-0000"))
      (libsource (lib "Q-Resistors") (part "RES0603 1/10W 5% 0 OHM"))
    )
    (comp (ref "R302")
      (value "0R")
      (footprint "0603-RW")
      (description "GP CHIP RES. 0 OHM 1/10W 5% 0603")
      (fields (field (name "POWER") "1/10W") (field (name "Comment") "QCF015030-0000"))
      (libsource (lib "Q-Resistors") (part "RES0603 1/10W 5% 0 OHM"))
    )
    (comp (ref "R303")
      (value "0R")
      (footprint "0603-RW")
      (description "GP CHIP RES. 0 OHM 1/10W 5% 0603")
      (fields (field (name "POWER") "1/10W") (field (name "Comment") "QCF015030-0000"))
      (libsource (lib "Q-Resistors") (part "RES0603 1/10W 5% 0 OHM"))
    )
    (comp (ref "R304")
      (value "0R")
      (footprint "0603-RW")
      (description "GP CHIP RES. 0 OHM 1/10W 5% 0603")
      (fields (field (name "POWER") "1/10W") (field (name "Comment") "QCF015030-0000"))
      (libsource (lib "Q-Resistors") (part "RES0603 1/10W 5% 0 OHM"))
    )
    (comp (ref "R305")
      (value "0R")
      (footprint "0603-RW")
      (description "GP CHIP RES. 0 OHM 1/10W 5% 0603")
      (fields (field (name "POWER") "1/10W") (field (name "Comment") "QCF015030-0000"))
      (libsource (lib "Q-Resistors") (part "RES0603 1/10W 5% 0 OHM"))
    )
    (comp (ref "R306")
      (value "0R")
      (footprint "0603-RW")
      (description "GP CHIP RES. 0 OHM 1/10W 5% 0603")
      (fields (field (name "POWER") "1/10W") (field (name "Comment") "QCF015030-0000"))
      (libsource (lib "Q-Resistors") (part "RES0603 1/10W 5% 0 OHM"))
    )
    (comp (ref "R307")
      (value "0R")
      (footprint "0603-RW")
      (description "GP CHIP RES. 0 OHM 1/10W 5% 0603")
      (fields (field (name "POWER") "1/10W") (field (name "Comment") "QCF015030-0000"))
      (libsource (lib "Q-Resistors") (part "RES0603 1/10W 5% 0 OHM"))
    )
    (comp (ref "R308")
      (value "0R")
      (footprint "0603-RW")
      (description "GP CHIP RES. 0 OHM 1/10W 5% 0603")
      (fields (field (name "POWER") "1/10W") (field (name "Comment") "QCF015030-0000"))
      (libsource (lib "Q-Resistors") (part "RES0603 1/10W 5% 0 OHM"))
    )
    (comp (ref "R309")
      (value "0R")
      (footprint "0603-RW")
      (description "GP CHIP RES. 0 OHM 1/10W 5% 0603")
      (fields (field (name "POWER") "1/10W") (field (name "Comment") "QCF015030-0000"))
      (libsource (lib "Q-Resistors") (part "RES0603 1/10W 5% 0 OHM"))
    )
    (comp (ref "R310")
      (value "0R")
      (footprint "0603-RW")
      (description "GP CHIP RES. 0 OHM 1/10W 5% 0603")
      (fields (field (name "POWER") "1/10W") (field (name "Comment") "QCF015030-0000"))
      (libsource (lib "Q-Resistors") (part "RES0603 1/10W 5% 0 OHM"))
    )
    (comp (ref "R311")
      (value "0R")
      (footprint "0603-RW")
      (description "GP CHIP RES. 0 OHM 1/10W 5% 0603")
      (fields (field (name "POWER") "1/10W") (field (name "Comment") "QCF015030-0000"))
      (libsource (lib "Q-Resistors") (part "RES0603 1/10W 5% 0 OHM"))
    )
    (comp (ref "R312")
      (value "0R")
      (footprint "0603-RW")
      (description "GP CHIP RES. 0 OHM 1/10W 5% 0603")
      (fields (field (name "POWER") "1/10W") (field (name "Comment") "QCF015030-0000"))
      (libsource (lib "Q-Resistors") (part "RES0603 1/10W 5% 0 OHM"))
    )
    (comp (ref "R313")
      (value "0R")
      (footprint "0603-RW")
      (description "GP CHIP RES. 0 OHM 1/10W 5% 0603")
      (fields (field (name "POWER") "1/10W") (field (name "Comment") "QCF015030-0000"))
      (libsource (lib "Q-Resistors") (part "RES0603 1/10W 5% 0 OHM"))
    )
    (comp (ref "SW1")
      (value "T670200011100")
      (footprint "TACT SW KFC-A06-09-16-250")
      (description "TACT SWITCH 50MA\\12VDC KFC-A06-09-16-2 K")
      (fields
        (field (name "MFG") "JIN JIA")
        (field (name "MFG PART") "KFC-A06-09-16-250")
        (field (name "CREATE_NAME") "Tom")
      )
      (libsource (lib "M-Controls") (part "TACT SW KFC-A06-09-16-250"))
    )
    (comp (ref "SW2")
      (value "T670600002700")
      (footprint "SS-23E03-G5 PA")
      (description "SLIDE SWITCH 8P SS-23E03-G PA K")
      (fields
        (field (name "MFG") "C&K")
        (field (name "VOLTAGE") "50V")
        (field (name "MFG PART") "SS-23E03-G5 PA")
        (field (name "CREATE_NAME") "Nathan")
      )
      (libsource (lib "M-Controls") (part "SS-23E03-G5 PA"))
    )
    (comp (ref "SW3")
      (value "T670600002700")
      (footprint "SS-23E03-G5 PA")
      (description "SLIDE SWITCH 8P SS-23E03-G PA K")
      (fields
        (field (name "MFG") "C&K")
        (field (name "VOLTAGE") "50V")
        (field (name "MFG PART") "SS-23E03-G5 PA")
        (field (name "CREATE_NAME") "Nathan")
      )
      (libsource (lib "M-Controls") (part "SS-23E03-G5 PA"))
    )
    (comp (ref "SW4")
      (value "T670200011100")
      (footprint "TACT SW KFC-A06-09-16-250")
      (description "TACT SWITCH 50MA\\12VDC KFC-A06-09-16-2 K")
      (fields
        (field (name "MFG") "JIN JIA")
        (field (name "MFG PART") "KFC-A06-09-16-250")
        (field (name "CREATE_NAME") "Tom")
      )
      (libsource (lib "M-Controls") (part "TACT SW KFC-A06-09-16-250"))
    )
    (comp (ref "TP1") (value "TP") (footprint "TP_1.0mm") (libsource (lib "Temporary") (part "TP")))
    (comp (ref "TP2") (value "TP") (footprint "TP_1.0mm") (libsource (lib "Temporary") (part "TP")))
    (comp (ref "TP3") (value "TP") (footprint "TP_1.0mm") (libsource (lib "Temporary") (part "TP")))
    (comp (ref "TP4") (value "TP") (footprint "TP_1.0mm") (libsource (lib "Temporary") (part "TP")))
    (comp (ref "TP5") (value "TP") (footprint "TP_1.0mm") (libsource (lib "Temporary") (part "TP")))
    (comp (ref "TP6") (value "TP") (footprint "TP_1.2mm") (libsource (lib "Temporary") (part "TP")))
    (comp (ref "TP7") (value "TP") (footprint "TP_1.0mm") (libsource (lib "Temporary") (part "TP")))
    (comp (ref "TP8") (value "TP") (footprint "TP_1.0mm") (libsource (lib "Temporary") (part "TP")))
    (comp (ref "TP9") (value "TP") (footprint "TP_1.0mm") (libsource (lib "Temporary") (part "TP")))
    (comp (ref "TP10") (value "TP") (footprint "TP_1.0mm") (libsource (lib "Temporary") (part "TP")))
    (comp (ref "TP11") (value "TP") (footprint "TP_1.0mm") (libsource (lib "Temporary") (part "TP")))
    (comp (ref "TP12") (value "TP") (footprint "TP_1.0mm") (libsource (lib "Temporary") (part "TP")))
    (comp (ref "TP13") (value "TP") (footprint "TP_1.0mm") (libsource (lib "Temporary") (part "TP")))
    (comp (ref "TP14") (value "TP") (footprint "TP_1.0mm") (libsource (lib "Temporary") (part "TP")))
    (comp (ref "TP15") (value "TP") (footprint "TP_1.0mm") (libsource (lib "Temporary") (part "TP")))
    (comp (ref "TP16") (value "TP") (footprint "TP_1.0mm") (libsource (lib "Temporary") (part "TP")))
    (comp (ref "TP17") (value "TP") (footprint "TP_1.0mm") (libsource (lib "Temporary") (part "TP")))
    (comp (ref "TP18") (value "TP") (footprint "TP_1.0mm") (libsource (lib "Temporary") (part "TP")))
    (comp (ref "TP19") (value "TP") (footprint "TP_1.0mm") (libsource (lib "Temporary") (part "TP")))
    (comp (ref "TP20") (value "TP") (footprint "TP_1.0mm") (libsource (lib "Temporary") (part "TP")))
    (comp (ref "TP21") (value "TP") (footprint "TP_1.0mm") (libsource (lib "Temporary") (part "TP")))
    (comp (ref "TP22") (value "TP") (footprint "TP_1.0mm") (libsource (lib "Temporary") (part "TP")))
    (comp (ref "TP23") (value "TP") (footprint "TP_1.0mm") (libsource (lib "Temporary") (part "TP")))
    (comp (ref "TP24") (value "TP") (footprint "TP_1.0mm") (libsource (lib "Temporary") (part "TP")))
    (comp (ref "TP25") (value "TP") (footprint "TP_1.0mm") (libsource (lib "Temporary") (part "TP")))
    (comp (ref "TP26") (value "TP") (footprint "TP_1.0mm") (libsource (lib "Temporary") (part "TP")))
    (comp (ref "TP27") (value "TP") (footprint "TP_1.0mm") (libsource (lib "Temporary") (part "TP")))
    (comp (ref "TP28") (value "TP") (footprint "TP_1.0mm") (libsource (lib "Temporary") (part "TP")))
    (comp (ref "TP29") (value "TP") (footprint "TP_1.0mm") (libsource (lib "Temporary") (part "TP")))
    (comp (ref "TP30") (value "TP") (footprint "TP_1.0mm") (libsource (lib "Temporary") (part "TP")))
    (comp (ref "TP31") (value "TP") (footprint "TP_1.0mm") (libsource (lib "Temporary") (part "TP")))
    (comp (ref "TP32") (value "TP") (footprint "TP_1.0mm") (libsource (lib "Temporary") (part "TP")))
    (comp (ref "TP33") (value "TP") (footprint "TP_1.0mm") (libsource (lib "Temporary") (part "TP")))
    (comp (ref "TP34") (value "TP") (footprint "TP_1.0mm") (libsource (lib "Temporary") (part "TP")))
    (comp (ref "TP35") (value "TP") (footprint "TP_1.0mm") (libsource (lib "Temporary") (part "TP")))
    (comp (ref "TP36") (value "TP") (footprint "TP_1.0mm") (libsource (lib "Temporary") (part "TP")))
    (comp (ref "TP37") (value "TP") (footprint "TP_1.0mm") (libsource (lib "Temporary") (part "TP")))
    (comp (ref "TP38") (value "TP") (footprint "TP_1.0mm") (libsource (lib "Temporary") (part "TP")))
    (comp (ref "TP39") (value "TP") (footprint "TP_1.0mm") (libsource (lib "Temporary") (part "TP")))
    (comp (ref "TP40") (value "TP") (footprint "TP_1.0mm") (libsource (lib "Temporary") (part "TP")))
    (comp (ref "TP41") (value "TP") (footprint "TP_1.0mm") (libsource (lib "Temporary") (part "TP")))
    (comp (ref "TP42") (value "TP") (footprint "TP_1.0mm") (libsource (lib "Temporary") (part "TP")))
    (comp (ref "TP43") (value "TP") (footprint "TP_1.0mm") (libsource (lib "Temporary") (part "TP")))
    (comp (ref "TP44") (value "TP") (footprint "TP_1.0mm") (libsource (lib "Temporary") (part "TP")))
    (comp (ref "TP45") (value "TP") (footprint "TP_1.0mm") (libsource (lib "Temporary") (part "TP")))
    (comp (ref "TP46") (value "TP") (footprint "TP_1.0mm") (libsource (lib "Temporary") (part "TP")))
    (comp (ref "TP47") (value "TP") (footprint "TP_1.0mm") (libsource (lib "Temporary") (part "TP")))
    (comp (ref "TP48") (value "TP") (footprint "TP_1.0mm") (libsource (lib "Temporary") (part "TP")))
    (comp (ref "TP49") (value "TP") (footprint "TP_1.0mm") (libsource (lib "Temporary") (part "TP")))
    (comp (ref "TP50") (value "TP") (footprint "TP_1.0mm") (libsource (lib "Temporary") (part "TP")))
    (comp (ref "TP51") (value "TP") (footprint "TP_1.0mm") (libsource (lib "Temporary") (part "TP")))
    (comp (ref "TP52") (value "TP") (footprint "TP_1.0mm") (libsource (lib "Temporary") (part "TP")))
    (comp (ref "TP53") (value "TP") (footprint "TP_1.0mm") (libsource (lib "Temporary") (part "TP")))
    (comp (ref "TP54") (value "TP") (footprint "TP_1.0mm") (libsource (lib "Temporary") (part "TP")))
    (comp (ref "TP55") (value "TP") (footprint "TP_1.0mm") (libsource (lib "Temporary") (part "TP")))
    (comp (ref "TP56") (value "TP") (footprint "TP_1.0mm") (libsource (lib "Temporary") (part "TP")))
    (comp (ref "TP57") (value "TP") (footprint "TP_1.0mm") (libsource (lib "Temporary") (part "TP")))
    (comp (ref "TP58") (value "TP") (footprint "TP_1.0mm") (libsource (lib "Temporary") (part "TP")))
    (comp (ref "TP59") (value "TP") (footprint "TP_1.0mm") (libsource (lib "Temporary") (part "TP")))
    (comp (ref "TP60") (value "TP") (footprint "TP_1.0mm") (libsource (lib "Temporary") (part "TP")))
    (comp (ref "TP61") (value "TP") (footprint "TP_1.0mm") (libsource (lib "Temporary") (part "TP")))
    (comp (ref "TP62") (value "TP") (footprint "TP_1.0mm") (libsource (lib "Temporary") (part "TP")))
    (comp (ref "TP63") (value "TP") (footprint "TP_1.0mm") (libsource (lib "Temporary") (part "TP")))
    (comp (ref "TP64") (value "TP") (footprint "TP_1.0mm") (libsource (lib "Temporary") (part "TP")))
    (comp (ref "TP65") (value "TP") (footprint "TP_1.0mm") (libsource (lib "Temporary") (part "TP")))
    (comp (ref "TP66") (value "TP") (footprint "TP_1.0mm") (libsource (lib "Temporary") (part "TP")))
    (comp (ref "TP67") (value "TP") (footprint "TP_1.0mm") (libsource (lib "Temporary") (part "TP")))
    (comp (ref "TP68") (value "TP") (footprint "TP_1.0mm") (libsource (lib "Temporary") (part "TP")))
    (comp (ref "TP69") (value "TP") (footprint "TP_1.0mm") (libsource (lib "Temporary") (part "TP")))
    (comp (ref "TP70") (value "TP") (footprint "TP_1.0mm") (libsource (lib "Temporary") (part "TP")))
    (comp (ref "TP71") (value "TP") (footprint "TP_1.0mm") (libsource (lib "Temporary") (part "TP")))
    (comp (ref "TP72") (value "TP") (footprint "TP_1.0mm") (libsource (lib "Temporary") (part "TP")))
    (comp (ref "TP73") (value "TP") (footprint "TP_1.0mm") (libsource (lib "Temporary") (part "TP")))
    (comp (ref "TP74") (value "TP") (footprint "TP_1.0mm") (libsource (lib "Temporary") (part "TP")))
    (comp (ref "TP75") (value "TP") (footprint "TP_1.0mm") (libsource (lib "Temporary") (part "TP")))
    (comp (ref "TP76") (value "TP") (footprint "TP_1.0mm") (libsource (lib "Temporary") (part "TP")))
    (comp (ref "TP77") (value "TP") (footprint "TP_1.0mm") (libsource (lib "Temporary") (part "TP")))
    (comp (ref "TP78") (value "TP") (footprint "TP_1.0mm") (libsource (lib "Temporary") (part "TP")))
    (comp (ref "TP79") (value "TP") (footprint "TP_1.0mm") (libsource (lib "Temporary") (part "TP")))
    (comp (ref "TP80") (value "TP") (footprint "TP_1.0mm") (libsource (lib "Temporary") (part "TP")))
    (comp (ref "TP81") (value "TP") (footprint "TP_1.0mm") (libsource (lib "Temporary") (part "TP")))
    (comp (ref "TP82") (value "TP") (footprint "TP_1.0mm") (libsource (lib "Temporary") (part "TP")))
    (comp (ref "TP83") (value "TP") (footprint "TP_1.0mm") (libsource (lib "Temporary") (part "TP")))
    (comp (ref "TP84") (value "TP") (footprint "TP_1.0mm") (libsource (lib "Temporary") (part "TP")))
    (comp (ref "TP85") (value "TP") (footprint "TP_1.0mm") (libsource (lib "Temporary") (part "TP")))
    (comp (ref "TP86") (value "TP") (footprint "TP_1.0mm") (libsource (lib "Temporary") (part "TP")))
    (comp (ref "TP87") (value "TP") (footprint "TP_1.0mm") (libsource (lib "Temporary") (part "TP")))
    (comp (ref "TP88") (value "TP") (footprint "TP_1.0mm") (libsource (lib "Temporary") (part "TP")))
    (comp (ref "TP89") (value "TP") (footprint "TP_1.0mm") (libsource (lib "Temporary") (part "TP")))
    (comp (ref "TP90") (value "TP") (footprint "TP_1.0mm") (libsource (lib "Temporary") (part "TP")))
    (comp (ref "TP91") (value "TP") (footprint "TP_1.0mm") (libsource (lib "Temporary") (part "TP")))
    (comp (ref "TP92") (value "TP") (footprint "TP_1.0mm") (libsource (lib "Temporary") (part "TP")))
    (comp (ref "TP93") (value "TP") (footprint "TP_1.0mm") (libsource (lib "Temporary") (part "TP")))
    (comp (ref "VR1")
      (value "MVRA02101-1030")
      (footprint "RV09BCF-40-25F-B10K")
      (description "ROTARY 10k OHM RV09BCF-40-25F-B10K")
      (fields
        (field (name "MFG") "艾华电子")
        (field (name "MFG PART") "RV09BCF-40-25F-B10K")
        (field (name "CREATE_NAME") "Evan@Deftronics")
      )
      (libsource (lib "M-Controls") (part "RV09BCF-40-25F-B10K"))
    )
    (comp (ref "VR2")
      (value "MVRA02101-1030")
      (footprint "RV09BCF-40-25F-B10K")
      (description "ROTARY 10k OHM RV09BCF-40-25F-B10K")
      (fields
        (field (name "MFG") "艾华电子")
        (field (name "MFG PART") "RV09BCF-40-25F-B10K")
        (field (name "CREATE_NAME") "Evan@Deftronics")
      )
      (libsource (lib "M-Controls") (part "RV09BCF-40-25F-B10K"))
    )
    (comp (ref "VR3")
      (value "MVRA02101-1030")
      (footprint "RV09BCF-40-25F-B10K")
      (description "ROTARY 10k OHM RV09BCF-40-25F-B10K")
      (fields
        (field (name "MFG") "艾华电子")
        (field (name "MFG PART") "RV09BCF-40-25F-B10K")
        (field (name "CREATE_NAME") "Evan@Deftronics")
      )
      (libsource (lib "M-Controls") (part "RV09BCF-40-25F-B10K"))
    )
    (comp (ref "VR4")
      (value "MVRA02101-1030")
      (footprint "RV09BCF-40-25F-B10K")
      (description "ROTARY 10k OHM RV09BCF-40-25F-B10K")
      (fields
        (field (name "MFG") "艾华电子")
        (field (name "MFG PART") "RV09BCF-40-25F-B10K")
        (field (name "CREATE_NAME") "Evan@Deftronics")
      )
      (libsource (lib "M-Controls") (part "RV09BCF-40-25F-B10K"))
    )
    (comp (ref "VR5")
      (value "MVRA02101-1030")
      (footprint "RV09BCF-40-25F-B10K")
      (description "ROTARY 10k OHM RV09BCF-40-25F-B10K")
      (fields
        (field (name "MFG") "艾华电子")
        (field (name "MFG PART") "RV09BCF-40-25F-B10K")
        (field (name "CREATE_NAME") "Evan@Deftronics")
      )
      (libsource (lib "M-Controls") (part "RV09BCF-40-25F-B10K"))
    )
    (comp (ref "VR6")
      (value "MVRA02101-1030")
      (footprint "RV09BCF-40-25F-B10K")
      (description "ROTARY 10k OHM RV09BCF-40-25F-B10K")
      (fields
        (field (name "MFG") "艾华电子")
        (field (name "MFG PART") "RV09BCF-40-25F-B10K")
        (field (name "CREATE_NAME") "Evan@Deftronics")
      )
      (libsource (lib "M-Controls") (part "RV09BCF-40-25F-B10K"))
    )
  )
  (nets
    (net (code "2") (name "+5V") (class "Default")
      (node (ref "D16") (pin "1") (pinfunction "A_1") (pintype "passive"))
    )
    (net (code "4") (name "+18V") (class "Default")
      (node (ref "R290") (pin "1") (pinfunction "1_1") (pintype "passive"))
      (node (ref "R291") (pin "2") (pinfunction "2_2") (pintype "passive"))
      (node (ref "TP45") (pin "1") (pinfunction "1_1") (pintype "passive"))
    )
    (net (code "7") (name "/AC_DET") (class "Default")
      (node (ref "C263") (pin "1") (pinfunction "1_1") (pintype "passive"))
      (node (ref "R301") (pin "2") (pinfunction "2_2") (pintype "passive"))
      (node (ref "TP55") (pin "1") (pinfunction "1_1") (pintype "passive"))
    )
    (net (code "13") (name "/AMP_CLIP_OTW") (class "Default")
      (node (ref "C264") (pin "1") (pinfunction "1_1") (pintype "passive"))
      (node (ref "R298") (pin "1") (pinfunction "1_1") (pintype "passive"))
      (node (ref "TP52") (pin "1") (pinfunction "1_1") (pintype "passive"))
    )
    (net (code "14") (name "/AMP_FAULT") (class "Default")
      (node (ref "C258") (pin "1") (pinfunction "1_1") (pintype "passive"))
      (node (ref "R300") (pin "1") (pinfunction "1_1") (pintype "passive"))
      (node (ref "TP54") (pin "1") (pinfunction "1_1") (pintype "passive"))
    )
    (net (code "15") (name "/AMP_NTC") (class "Default")
      (node (ref "C257") (pin "1") (pinfunction "1_1") (pintype "passive"))
      (node (ref "R296") (pin "1") (pinfunction "1_1") (pintype "passive"))
      (node (ref "TP51") (pin "1") (pinfunction "1_1") (pintype "passive"))
    )
    (net (code "16") (name "/AMP_RESET") (class "Default")
      (node (ref "C265") (pin "1") (pinfunction "1_1") (pintype "passive"))
      (node (ref "R302") (pin "1") (pinfunction "1_1") (pintype "passive"))
      (node (ref "TP56") (pin "1") (pinfunction "1_1") (pintype "passive"))
    )
    (net (code "17") (name "/ARRAY_DAC_N") (class "Default")
      (node (ref "C267") (pin "1") (pinfunction "1_1") (pintype "passive"))
      (node (ref "R312") (pin "1") (pinfunction "1_1") (pintype "passive"))
      (node (ref "TP77") (pin "1") (pinfunction "1_1") (pintype "passive"))
    )
    (net (code "18") (name "/ARRAY_DAC_P") (class "Default")
      (node (ref "C268") (pin "1") (pinfunction "1_1") (pintype "passive"))
      (node (ref "R313") (pin "2") (pinfunction "2_2") (pintype "passive"))
      (node (ref "TP78") (pin "1") (pinfunction "1_1") (pintype "passive"))
    )
    (net (code "19") (name "/AUXIN_DET") (class "Default")
      (node (ref "C64") (pin "1") (pinfunction "1_1") (pintype "passive"))
      (node (ref "PJ1") (pin "4") (pinfunction "4_4") (pintype "passive"))
      (node (ref "TP42") (pin "1") (pinfunction "1_1") (pintype "passive"))
    )
    (net (code "20") (name "/AUXIN_VOL") (class "Default")
      (node (ref "C65") (pin "1") (pinfunction "1_1") (pintype "passive"))
      (node (ref "J9") (pin "5") (pinfunction "5_5") (pintype "passive"))
      (node (ref "TP84") (pin "1") (pinfunction "1_1") (pintype "passive"))
    )
    (net (code "21") (name "/AUX_L") (class "Default")
      (node (ref "PJ1") (pin "2") (pinfunction "2_2") (pintype "passive"))
      (node (ref "TP40") (pin "1") (pinfunction "1_1") (pintype "passive"))
    )
    (net (code "22") (name "/AUX_R") (class "Default")
      (node (ref "PJ1") (pin "3") (pinfunction "3_3") (pintype "passive"))
      (node (ref "TP41") (pin "1") (pinfunction "1_1") (pintype "passive"))
    )
    (net (code "23") (name "/BAT_VOLT_CH") (class "Default")
      (node (ref "C266") (pin "1") (pinfunction "1_1") (pintype "passive"))
      (node (ref "R306") (pin "1") (pinfunction "1_1") (pintype "passive"))
      (node (ref "TP62") (pin "1") (pinfunction "1_1") (pintype "passive"))
    )
    (net (code "24") (name "/BOOST_EN") (class "Default")
      (node (ref "C262") (pin "1") (pinfunction "1_1") (pintype "passive"))
      (node (ref "R305") (pin "2") (pinfunction "2_2") (pintype "passive"))
      (node (ref "TP59") (pin "1") (pinfunction "1_1") (pintype "passive"))
    )
    (net (code "26") (name "/BT_Pair") (class "Default")
      (node (ref "C57") (pin "2") (pinfunction "2_2") (pintype "passive"))
      (node (ref "R277") (pin "1") (pinfunction "1_1") (pintype "passive"))
      (node (ref "R89") (pin "1") (pinfunction "1_1") (pintype "passive"))
      (node (ref "TP20") (pin "1") (pinfunction "1_1") (pintype "passive"))
    )
    (net (code "29") (name "/CH1_BASS") (class "Default")
      (node (ref "R76") (pin "1") (pinfunction "1_1") (pintype "passive"))
      (node (ref "TP10") (pin "1") (pinfunction "1_1") (pintype "passive"))
    )
    (net (code "30") (name "/CH1_LIM") (class "Default")
      (node (ref "C75") (pin "2") (pinfunction "2_2") (pintype "passive"))
      (node (ref "J9") (pin "10") (pinfunction "10_10") (pintype "passive"))
      (node (ref "TP65") (pin "1") (pinfunction "1_1") (pintype "passive"))
    )
    (net (code "31") (name "/CH1_LINE_DET") (class "Default")
      (node (ref "J2") (pin "SN") (pinfunction "SN_SN") (pintype "passive"))
      (node (ref "TP22") (pin "1") (pinfunction "1_1") (pintype "passive"))
    )
    (net (code "32") (name "/CH1_LINE_N") (class "Default")
      (node (ref "J2") (pin "R") (pinfunction "R_R") (pintype "passive"))
      (node (ref "TP21") (pin "1") (pinfunction "1_1") (pintype "passive"))
    )
    (net (code "33") (name "/CH1_LINE_P") (class "Default")
      (node (ref "J2") (pin "T") (pinfunction "T_T") (pintype "passive"))
      (node (ref "TP23") (pin "1") (pinfunction "1_1") (pintype "passive"))
    )
    (net (code "34") (name "/CH1_MIC_N") (class "Default")
      (node (ref "J2") (pin "3") (pinfunction "3_3") (pintype "passive"))
      (node (ref "TP25") (pin "1") (pinfunction "1_1") (pintype "passive"))
    )
    (net (code "35") (name "/CH1_MIC_P") (class "Default")
      (node (ref "J2") (pin "2") (pinfunction "2_2") (pintype "passive"))
      (node (ref "TP27") (pin "1") (pinfunction "1_1") (pintype "passive"))
    )
    (net (code "36") (name "/CH1_REVERB") (class "Default")
      (node (ref "R78") (pin "1") (pinfunction "1_1") (pintype "passive"))
      (node (ref "TP11") (pin "1") (pinfunction "1_1") (pintype "passive"))
    )
    (net (code "37") (name "/CH1_SIG") (class "Default")
      (node (ref "C74") (pin "2") (pinfunction "2_2") (pintype "passive"))
      (node (ref "J9") (pin "11") (pinfunction "11_11") (pintype "passive"))
      (node (ref "TP61") (pin "1") (pinfunction "1_1") (pintype "passive"))
    )
    (net (code "38") (name "/CH1_TM_GUITAR") (class "Default")
      (node (ref "C52") (pin "1") (pinfunction "1_1") (pintype "passive"))
      (node (ref "R70") (pin "1") (pinfunction "1_1") (pintype "passive"))
      (node (ref "SW2") (pin "3") (pinfunction "3_3") (pintype "passive"))
      (node (ref "SW2") (pin "6") (pinfunction "6_6") (pintype "passive"))
      (node (ref "TP14") (pin "1") (pinfunction "1_1") (pintype "passive"))
    )
    (net (code "39") (name "/CH1_TM_MIC") (class "Default")
      (node (ref "C53") (pin "1") (pinfunction "1_1") (pintype "passive"))
      (node (ref "R71") (pin "1") (pinfunction "1_1") (pintype "passive"))
      (node (ref "SW2") (pin "4") (pinfunction "4_4") (pintype "passive"))
      (node (ref "SW2") (pin "5") (pinfunction "5_5") (pintype "passive"))
      (node (ref "TP7") (pin "1") (pinfunction "1_1") (pintype "passive"))
    )
    (net (code "40") (name "/CH1_TREBLE") (class "Default")
      (node (ref "R74") (pin "1") (pinfunction "1_1") (pintype "passive"))
      (node (ref "TP9") (pin "1") (pinfunction "1_1") (pintype "passive"))
    )
    (net (code "41") (name "/CH2_BASS") (class "Default")
      (node (ref "R85") (pin "1") (pinfunction "1_1") (pintype "passive"))
      (node (ref "TP17") (pin "1") (pinfunction "1_1") (pintype "passive"))
    )
    (net (code "42") (name "/CH2_LIM") (class "Default")
      (node (ref "C77") (pin "2") (pinfunction "2_2") (pintype "passive"))
      (node (ref "J9") (pin "8") (pinfunction "8_8") (pintype "passive"))
      (node (ref "TP72") (pin "1") (pinfunction "1_1") (pintype "passive"))
    )
    (net (code "43") (name "/CH2_LINE_DET") (class "Default")
      (node (ref "J4") (pin "SN") (pinfunction "SN_SN") (pintype "passive"))
      (node (ref "TP31") (pin "1") (pinfunction "1_1") (pintype "passive"))
    )
    (net (code "44") (name "/CH2_LINE_N") (class "Default")
      (node (ref "J4") (pin "R") (pinfunction "R_R") (pintype "passive"))
      (node (ref "TP30") (pin "1") (pinfunction "1_1") (pintype "passive"))
    )
    (net (code "45") (name "/CH2_LINE_P") (class "Default")
      (node (ref "J4") (pin "T") (pinfunction "T_T") (pintype "passive"))
      (node (ref "TP34") (pin "1") (pinfunction "1_1") (pintype "passive"))
    )
    (net (code "46") (name "/CH2_MIC_N") (class "Default")
      (node (ref "J4") (pin "3") (pinfunction "3_3") (pintype "passive"))
      (node (ref "TP35") (pin "1") (pinfunction "1_1") (pintype "passive"))
    )
    (net (code "47") (name "/CH2_MIC_P") (class "Default")
      (node (ref "J4") (pin "2") (pinfunction "2_2") (pintype "passive"))
      (node (ref "TP36") (pin "1") (pinfunction "1_1") (pintype "passive"))
    )
    (net (code "48") (name "/CH2_REVERB") (class "Default")
      (node (ref "R87") (pin "1") (pinfunction "1_1") (pintype "passive"))
      (node (ref "TP18") (pin "1") (pinfunction "1_1") (pintype "passive"))
    )
    (net (code "49") (name "/CH2_SIG") (class "Default")
      (node (ref "C76") (pin "2") (pinfunction "2_2") (pintype "passive"))
      (node (ref "J9") (pin "9") (pinfunction "9_9") (pintype "passive"))
      (node (ref "TP67") (pin "1") (pinfunction "1_1") (pintype "passive"))
    )
    (net (code "50") (name "/CH2_TM_GUITAR") (class "Default")
      (node (ref "C54") (pin "1") (pinfunction "1_1") (pintype "passive"))
      (node (ref "R72") (pin "1") (pinfunction "1_1") (pintype "passive"))
      (node (ref "SW3") (pin "3") (pinfunction "3_3") (pintype "passive"))
      (node (ref "SW3") (pin "6") (pinfunction "6_6") (pintype "passive"))
      (node (ref "TP15") (pin "1") (pinfunction "1_1") (pintype "passive"))
    )
    (net (code "51") (name "/CH2_TM_MIC") (class "Default")
      (node (ref "C55") (pin "1") (pinfunction "1_1") (pintype "passive"))
      (node (ref "R73") (pin "1") (pinfunction "1_1") (pintype "passive"))
      (node (ref "SW3") (pin "4") (pinfunction "4_4") (pintype "passive"))
      (node (ref "SW3") (pin "5") (pinfunction "5_5") (pintype "passive"))
      (node (ref "TP8") (pin "1") (pinfunction "1_1") (pintype "passive"))
    )
    (net (code "52") (name "/CH2_TREBLE") (class "Default")
      (node (ref "R83") (pin "1") (pinfunction "1_1") (pintype "passive"))
      (node (ref "TP16") (pin "1") (pinfunction "1_1") (pintype "passive"))
    )
    (net (code "53") (name "/CH3_LIM") (class "Default")
      (node (ref "C79") (pin "2") (pinfunction "2_2") (pintype "passive"))
      (node (ref "J9") (pin "6") (pinfunction "6_6") (pintype "passive"))
      (node (ref "TP80") (pin "1") (pinfunction "1_1") (pintype "passive"))
    )
    (net (code "54") (name "/CH3_SIG") (class "Default")
      (node (ref "C78") (pin "2") (pinfunction "2_2") (pintype "passive"))
      (node (ref "J9") (pin "7") (pinfunction "7_7") (pintype "passive"))
      (node (ref "TP75") (pin "1") (pinfunction "1_1") (pintype "passive"))
    )
    (net (code "55") (name "/CHR_CURR_SW") (class "Default")
      (node (ref "C259") (pin "1") (pinfunction "1_1") (pintype "passive"))
      (node (ref "R304") (pin "1") (pinfunction "1_1") (pintype "passive"))
      (node (ref "TP58") (pin "1") (pinfunction "1_1") (pintype "passive"))
    )
    (net (code "56") (name "/CHR_EN") (class "Default")
      (node (ref "C269") (pin "1") (pinfunction "1_1") (pintype "passive"))
      (node (ref "R307") (pin "2") (pinfunction "2_2") (pintype "passive"))
      (node (ref "TP63") (pin "1") (pinfunction "1_1") (pintype "passive"))
    )
    (net (code "57") (name "/CLK") (class "Default")
      (node (ref "J7") (pin "2") (pinfunction "2_2") (pintype "passive"))
      (node (ref "TP81") (pin "1") (pinfunction "1_1") (pintype "passive"))
    )
    (net (code "58") (name "/DEBUG_SCL") (class "Default")
      (node (ref "J8") (pin "3") (pinfunction "3_3") (pintype "passive"))
    )
    (net (code "59") (name "/DEBUG_SDA") (class "Default")
      (node (ref "J8") (pin "4") (pinfunction "4_4") (pintype "passive"))
    )
    (net (code "60") (name "/FLED") (class "Default")
      (node (ref "C58") (pin "2") (pinfunction "2_2") (pintype "passive"))
      (node (ref "J1") (pin "8") (pinfunction "8_8") (pintype "passive"))
      (node (ref "TP24") (pin "1") (pinfunction "1_1") (pintype "passive"))
    )
    (net (code "61") (name "/I2C_SCL") (class "Default")
      (node (ref "R91") (pin "2") (pinfunction "2_2") (pintype "passive"))
      (node (ref "R95") (pin "1") (pinfunction "1_1") (pintype "passive"))
      (node (ref "TP33") (pin "1") (pinfunction "1_1") (pintype "passive"))
    )
    (net (code "62") (name "/I2C_SDA") (class "Default")
      (node (ref "R93") (pin "2") (pinfunction "2_2") (pintype "passive"))
      (node (ref "R94") (pin "1") (pinfunction "1_1") (pintype "passive"))
      (node (ref "TP32") (pin "1") (pinfunction "1_1") (pintype "passive"))
    )
    (net (code "63") (name "/LINE_OUT_N") (class "Default")
      (node (ref "J6") (pin "3") (pinfunction "3_3") (pintype "passive"))
      (node (ref "TP43") (pin "1") (pinfunction "1_1") (pintype "passive"))
    )
    (net (code "64") (name "/LINE_OUT_P") (class "Default")
      (node (ref "J6") (pin "2") (pinfunction "2_2") (pintype "passive"))
      (node (ref "TP50") (pin "1") (pinfunction "1_1") (pintype "passive"))
    )
    (net (code "67") (name "/MISO") (class "Default")
      (node (ref "J7") (pin "4") (pinfunction "4_4") (pintype "passive"))
      (node (ref "TP73") (pin "1") (pinfunction "1_1") (pintype "passive"))
    )
    (net (code "68") (name "/MOSI") (class "Default")
      (node (ref "J7") (pin "3") (pinfunction "3_3") (pintype "passive"))
      (node (ref "TP76") (pin "1") (pinfunction "1_1") (pintype "passive"))
    )
    (net (code "69") (name "/ON_STBY") (class "Default")
      (node (ref "C270") (pin "1") (pinfunction "1_1") (pintype "passive"))
      (node (ref "R303") (pin "2") (pinfunction "2_2") (pintype "passive"))
      (node (ref "TP57") (pin "1") (pinfunction "1_1") (pintype "passive"))
    )
    (net (code "70") (name "/PLED_B") (class "Default")
      (node (ref "LED1") (pin "4") (pinfunction "4_4") (pintype "passive"))
      (node (ref "TP13") (pin "1") (pinfunction "1_1") (pintype "passive"))
    )
    (net (code "71") (name "/PLED_R") (class "Default")
      (node (ref "LED1") (pin "2") (pinfunction "2_2") (pintype "passive"))
      (node (ref "TP4") (pin "1") (pinfunction "1_1") (pintype "passive"))
    )
    (net (code "72") (name "/POLE_SW") (class "Default")
      (node (ref "C59") (pin "2") (pinfunction "2_2") (pintype "passive"))
      (node (ref "R90") (pin "1") (pinfunction "1_1") (pintype "passive"))
      (node (ref "R92") (pin "1") (pinfunction "1_1") (pintype "passive"))
      (node (ref "TP28") (pin "1") (pinfunction "1_1") (pintype "passive"))
    )
    (net (code "73") (name "/POT12") (class "Default")
      (node (ref "B2") (pin "1") (pinfunction "1_1") (pintype "passive"))
      (node (ref "J9") (pin "21") (pinfunction "21_21") (pintype "passive"))
      (node (ref "TP64") (pin "1") (pinfunction "1_1") (pintype "passive"))
    )
    (net (code "74") (name "/POT12F") (class "Default")
      (node (ref "B2") (pin "2") (pinfunction "2_2") (pintype "passive"))
      (node (ref "C72") (pin "1") (pinfunction "1_1") (pintype "passive"))
    )
    (net (code "75") (name "/POT13") (class "Default")
      (node (ref "B1") (pin "1") (pinfunction "1_1") (pintype "passive"))
      (node (ref "J9") (pin "22") (pinfunction "22_22") (pintype "passive"))
      (node (ref "TP60") (pin "1") (pinfunction "1_1") (pintype "passive"))
    )
    (net (code "76") (name "/POT13F") (class "Default")
      (node (ref "B1") (pin "2") (pinfunction "2_2") (pintype "passive"))
      (node (ref "C73") (pin "1") (pinfunction "1_1") (pintype "passive"))
    )
    (net (code "77") (name "/POT15") (class "Default")
      (node (ref "C71") (pin "1") (pinfunction "1_1") (pintype "passive"))
      (node (ref "J9") (pin "19") (pinfunction "19_19") (pintype "passive"))
      (node (ref "TP71") (pin "1") (pinfunction "1_1") (pintype "passive"))
    )
    (net (code "78") (name "/POT16") (class "Default")
      (node (ref "C70") (pin "1") (pinfunction "1_1") (pintype "passive"))
      (node (ref "J9") (pin "18") (pinfunction "18_18") (pintype "passive"))
      (node (ref "TP74") (pin "1") (pinfunction "1_1") (pintype "passive"))
    )
    (net (code "79") (name "/POT22") (class "Default")
      (node (ref "B3") (pin "1") (pinfunction "1_1") (pintype "passive"))
      (node (ref "J9") (pin "14") (pinfunction "14_14") (pintype "passive"))
      (node (ref "TP90") (pin "1") (pinfunction "1_1") (pintype "passive"))
    )
    (net (code "80") (name "/POT22F") (class "Default")
      (node (ref "B3") (pin "2") (pinfunction "2_2") (pintype "passive"))
      (node (ref "C67") (pin "1") (pinfunction "1_1") (pintype "passive"))
    )
    (net (code "81") (name "/POT23") (class "Default")
      (node (ref "B4") (pin "1") (pinfunction "1_1") (pintype "passive"))
      (node (ref "J9") (pin "13") (pinfunction "13_13") (pintype "passive"))
      (node (ref "TP92") (pin "1") (pinfunction "1_1") (pintype "passive"))
    )
    (net (code "82") (name "/POT23F") (class "Default")
      (node (ref "B4") (pin "2") (pinfunction "2_2") (pintype "passive"))
      (node (ref "C66") (pin "1") (pinfunction "1_1") (pintype "passive"))
    )
    (net (code "83") (name "/POT25") (class "Default")
      (node (ref "C68") (pin "1") (pinfunction "1_1") (pintype "passive"))
      (node (ref "J9") (pin "16") (pinfunction "16_16") (pintype "passive"))
      (node (ref "TP83") (pin "1") (pinfunction "1_1") (pintype "passive"))
    )
    (net (code "84") (name "/POT26") (class "Default")
      (node (ref "C69") (pin "1") (pinfunction "1_1") (pintype "passive"))
      (node (ref "J9") (pin "17") (pinfunction "17_17") (pintype "passive"))
      (node (ref "TP79") (pin "1") (pinfunction "1_1") (pintype "passive"))
    )
    (net (code "85") (name "/PS_ON") (class "Default")
      (node (ref "C51") (pin "2") (pinfunction "2_2") (pintype "passive"))
      (node (ref "R276") (pin "1") (pinfunction "1_1") (pintype "passive"))
      (node (ref "R81") (pin "1") (pinfunction "1_1") (pintype "passive"))
      (node (ref "TP6") (pin "1") (pinfunction "1_1") (pintype "passive"))
    )
    (net (code "88") (name "/SPI_CS#") (class "Default")
      (node (ref "J7") (pin "5") (pinfunction "5_5") (pintype "passive"))
      (node (ref "TP68") (pin "1") (pinfunction "1_1") (pintype "passive"))
    )
    (net (code "89") (name "/USB_D_N") (class "Default")
      (node (ref "C63") (pin "1") (pinfunction "1_1") (pintype "passive"))
      (node (ref "D15") (pin "1") (pinfunction "1_1") (pintype "passive"))
      (node (ref "J3") (pin "3") (pinfunction "3_3") (pintype "passive"))
      (node (ref "TP38") (pin "1") (pinfunction "1_1") (pintype "passive"))
    )
    (net (code "90") (name "/USB_D_P") (class "Default")
      (node (ref "C62") (pin "1") (pinfunction "1_1") (pintype "passive"))
      (node (ref "D14") (pin "1") (pinfunction "1_1") (pintype "passive"))
      (node (ref "J3") (pin "5") (pinfunction "5_5") (pintype "passive"))
      (node (ref "TP39") (pin "1") (pinfunction "1_1") (pintype "passive"))
    )
    (net (code "91") (name "/VCHG") (class "Default")
      (node (ref "D13") (pin "2") (pinfunction "K_2") (pintype "passive"))
      (node (ref "TP37") (pin "1") (pinfunction "1_1") (pintype "passive"))
    )
    (net (code "92") (name "/WF_DAC_N") (class "Default")
      (node (ref "C260") (pin "1") (pinfunction "1_1") (pintype "passive"))
      (node (ref "R310") (pin "1") (pinfunction "1_1") (pintype "passive"))
      (node (ref "TP69") (pin "1") (pinfunction "1_1") (pintype "passive"))
    )
    (net (code "93") (name "/WF_DAC_P") (class "Default")
      (node (ref "C261") (pin "1") (pinfunction "1_1") (pintype "passive"))
      (node (ref "R311") (pin "2") (pinfunction "2_2") (pintype "passive"))
      (node (ref "TP70") (pin "1") (pinfunction "1_1") (pintype "passive"))
    )
    (net (code "95") (name "3.3V") (class "Default")
      (node (ref "R70") (pin "2") (pinfunction "2_2") (pintype "passive"))
      (node (ref "R71") (pin "2") (pinfunction "2_2") (pintype "passive"))
      (node (ref "R72") (pin "2") (pinfunction "2_2") (pintype "passive"))
      (node (ref "R73") (pin "2") (pinfunction "2_2") (pintype "passive"))
      (node (ref "R75") (pin "2") (pinfunction "2_2") (pintype "passive"))
      (node (ref "R77") (pin "2") (pinfunction "2_2") (pintype "passive"))
      (node (ref "R79") (pin "2") (pinfunction "2_2") (pintype "passive"))
      (node (ref "R84") (pin "2") (pinfunction "2_2") (pintype "passive"))
      (node (ref "R86") (pin "2") (pinfunction "2_2") (pintype "passive"))
      (node (ref "R88") (pin "2") (pinfunction "2_2") (pintype "passive"))
      (node (ref "TP1") (pin "1") (pinfunction "1_1") (pintype "passive"))
      (node (ref "TP2") (pin "1") (pinfunction "1_1") (pintype "passive"))
      (node (ref "TP3") (pin "1") (pinfunction "1_1") (pintype "passive"))
    )
    (net (code "96") (name "BT_3.3V") (class "Default")
      (node (ref "R297") (pin "2") (pinfunction "2_2") (pintype "passive"))
      (node (ref "TP49") (pin "1") (pinfunction "1_1") (pintype "passive"))
    )
    (net (code "97") (name "D_1.2V") (class "Default")
      (node (ref "J9") (pin "4") (pinfunction "4_4") (pintype "passive"))
      (node (ref "TP87") (pin "1") (pinfunction "1_1") (pintype "passive"))
    )
    (net (code "98") (name "GND") (class "Default")
      (node (ref "C257") (pin "2") (pinfunction "2_2") (pintype "passive"))
      (node (ref "C258") (pin "2") (pinfunction "2_2") (pintype "passive"))
      (node (ref "C259") (pin "2") (pinfunction "2_2") (pintype "passive"))
      (node (ref "C260") (pin "2") (pinfunction "2_2") (pintype "passive"))
      (node (ref "C261") (pin "2") (pinfunction "2_2") (pintype "passive"))
      (node (ref "C262") (pin "2") (pinfunction "2_2") (pintype "passive"))
      (node (ref "C263") (pin "2") (pinfunction "2_2") (pintype "passive"))
      (node (ref "C264") (pin "2") (pinfunction "2_2") (pintype "passive"))
      (node (ref "C265") (pin "2") (pinfunction "2_2") (pintype "passive"))
      (node (ref "C266") (pin "2") (pinfunction "2_2") (pintype "passive"))
      (node (ref "C267") (pin "2") (pinfunction "2_2") (pintype "passive"))
      (node (ref "C268") (pin "2") (pinfunction "2_2") (pintype "passive"))
      (node (ref "C269") (pin "2") (pinfunction "2_2") (pintype "passive"))
      (node (ref "C270") (pin "2") (pinfunction "2_2") (pintype "passive"))
      (node (ref "C271") (pin "2") (pinfunction "2_2") (pintype "passive"))
      (node (ref "C50") (pin "2") (pinfunction "2_2") (pintype "passive"))
      (node (ref "C51") (pin "1") (pinfunction "1_1") (pintype "passive"))
      (node (ref "C52") (pin "2") (pinfunction "2_2") (pintype "passive"))
      (node (ref "C53") (pin "2") (pinfunction "2_2") (pintype "passive"))
      (node (ref "C54") (pin "2") (pinfunction "2_2") (pintype "passive"))
      (node (ref "C55") (pin "2") (pinfunction "2_2") (pintype "passive"))
      (node (ref "C56") (pin "2") (pinfunction "2_2") (pintype "passive"))
      (node (ref "C57") (pin "1") (pinfunction "1_1") (pintype "passive"))
      (node (ref "C58") (pin "1") (pinfunction "1_1") (pintype "passive"))
      (node (ref "C59") (pin "1") (pinfunction "1_1") (pintype "passive"))
      (node (ref "C60") (pin "1") (pinfunction "1_1") (pintype "passive"))
      (node (ref "C61") (pin "1") (pinfunction "1_1") (pintype "passive"))
      (node (ref "C62") (pin "2") (pinfunction "2_2") (pintype "passive"))
      (node (ref "C63") (pin "2") (pinfunction "2_2") (pintype "passive"))
      (node (ref "C64") (pin "2") (pinfunction "2_2") (pintype "passive"))
      (node (ref "C65") (pin "2") (pinfunction "2_2") (pintype "passive"))
      (node (ref "C66") (pin "2") (pinfunction "2_2") (pintype "passive"))
      (node (ref "C67") (pin "2") (pinfunction "2_2") (pintype "passive"))
      (node (ref "C68") (pin "2") (pinfunction "2_2") (pintype "passive"))
      (node (ref "C69") (pin "2") (pinfunction "2_2") (pintype "passive"))
      (node (ref "C70") (pin "2") (pinfunction "2_2") (pintype "passive"))
      (node (ref "C71") (pin "2") (pinfunction "2_2") (pintype "passive"))
      (node (ref "C72") (pin "2") (pinfunction "2_2") (pintype "passive"))
      (node (ref "C73") (pin "2") (pinfunction "2_2") (pintype "passive"))
      (node (ref "C74") (pin "1") (pinfunction "1_1") (pintype "passive"))
      (node (ref "C75") (pin "1") (pinfunction "1_1") (pintype "passive"))
      (node (ref "C76") (pin "1") (pinfunction "1_1") (pintype "passive"))
      (node (ref "C77") (pin "1") (pinfunction "1_1") (pintype "passive"))
      (node (ref "C78") (pin "1") (pinfunction "1_1") (pintype "passive"))
      (node (ref "C79") (pin "1") (pinfunction "1_1") (pintype "passive"))
      (node (ref "D11") (pin "1") (pinfunction "1_1") (pintype "passive"))
      (node (ref "D12") (pin "1") (pinfunction "1_1") (pintype "passive"))
      (node (ref "D14") (pin "2") (pinfunction "2_2") (pintype "passive"))
      (node (ref "D15") (pin "2") (pinfunction "2_2") (pintype "passive"))
      (node (ref "J1") (pin "1") (pinfunction "1_1") (pintype "passive"))
      (node (ref "J1") (pin "4") (pinfunction "4_4") (pintype "passive"))
      (node (ref "J2") (pin "1") (pinfunction "1_1") (pintype "passive"))
      (node (ref "J2") (pin "G") (pinfunction "G_G") (pintype "passive"))
      (node (ref "J2") (pin "RN") (pinfunction "RN_RN") (pintype "passive"))
      (node (ref "J2") (pin "S") (pinfunction "S_S") (pintype "passive"))
      (node (ref "J2") (pin "TN") (pinfunction "TN_TN") (pintype "passive"))
      (node (ref "J3") (pin "2") (pinfunction "2_2") (pintype "passive"))
      (node (ref "J3") (pin "4") (pinfunction "4_4") (pintype "passive"))
      (node (ref "J3") (pin "6") (pinfunction "6_6") (pintype "passive"))
      (node (ref "J3") (pin "8") (pinfunction "8_8") (pintype "passive"))
      (node (ref "J4") (pin "1") (pinfunction "1_1") (pintype "passive"))
      (node (ref "J4") (pin "G") (pinfunction "G_G") (pintype "passive"))
      (node (ref "J4") (pin "RN") (pinfunction "RN_RN") (pintype "passive"))
      (node (ref "J4") (pin "S") (pinfunction "S_S") (pintype "passive"))
      (node (ref "J4") (pin "TN") (pinfunction "TN_TN") (pintype "passive"))
      (node (ref "J6") (pin "1") (pinfunction "1_1") (pintype "passive"))
      (node (ref "J6") (pin "4") (pinfunction "4_4") (pintype "passive"))
      (node (ref "J7") (pin "1") (pinfunction "1_1") (pintype "passive"))
      (node (ref "J8") (pin "1") (pinfunction "1_1") (pintype "passive"))
      (node (ref "J9") (pin "0") (pinfunction "0_0") (pintype "passive"))
      (node (ref "J9") (pin "1") (pinfunction "1_1") (pintype "passive"))
      (node (ref "J9") (pin "12") (pinfunction "12_12") (pintype "passive"))
      (node (ref "J9") (pin "15") (pinfunction "15_15") (pintype "passive"))
      (node (ref "J9") (pin "2") (pinfunction "2_2") (pintype "passive"))
      (node (ref "J9") (pin "20") (pinfunction "20_20") (pintype "passive"))
      (node (ref "PJ1") (pin "1") (pinfunction "1_1") (pintype "passive"))
      (node (ref "PJ1") (pin "5") (pinfunction "5_5") (pintype "passive"))
      (node (ref "R292") (pin "1") (pinfunction "1_1") (pintype "passive"))
      (node (ref "R293") (pin "2") (pinfunction "2_2") (pintype "passive"))
      (node (ref "R295") (pin "2") (pinfunction "2_2") (pintype "passive"))
      (node (ref "R308") (pin "1") (pinfunction "1_1") (pintype "passive"))
      (node (ref "R309") (pin "2") (pinfunction "2_2") (pintype "passive"))
      (node (ref "R81") (pin "2") (pinfunction "2_2") (pintype "passive"))
      (node (ref "R89") (pin "2") (pinfunction "2_2") (pintype "passive"))
      (node (ref "R92") (pin "2") (pinfunction "2_2") (pintype "passive"))
      (node (ref "SW2") (pin "2") (pinfunction "2_2") (pintype "passive"))
      (node (ref "SW2") (pin "7") (pinfunction "7_7") (pintype "passive"))
      (node (ref "SW3") (pin "2") (pinfunction "2_2") (pintype "passive"))
      (node (ref "SW3") (pin "7") (pinfunction "7_7") (pintype "passive"))
      (node (ref "TP46") (pin "1") (pinfunction "1_1") (pintype "passive"))
      (node (ref "TP47") (pin "1") (pinfunction "1_1") (pintype "passive"))
      (node (ref "TP48") (pin "1") (pinfunction "1_1") (pintype "passive"))
      (node (ref "TP82") (pin "1") (pinfunction "1_1") (pintype "passive"))
      (node (ref "TP85") (pin "1") (pinfunction "1_1") (pintype "passive"))
      (node (ref "TP86") (pin "1") (pinfunction "1_1") (pintype "passive"))
      (node (ref "TP88") (pin "1") (pinfunction "1_1") (pintype "passive"))
      (node (ref "TP89") (pin "1") (pinfunction "1_1") (pintype "passive"))
      (node (ref "TP93") (pin "1") (pinfunction "1_1") (pintype "passive"))
      (node (ref "VR1") (pin "1") (pinfunction "1_1") (pintype "passive"))
      (node (ref "VR2") (pin "1") (pinfunction "1_1") (pintype "passive"))
      (node (ref "VR3") (pin "1") (pinfunction "1_1") (pintype "passive"))
      (node (ref "VR4") (pin "1") (pinfunction "1_1") (pintype "passive"))
      (node (ref "VR5") (pin "1") (pinfunction "1_1") (pintype "passive"))
      (node (ref "VR6") (pin "1") (pinfunction "1_1") (pintype "passive"))
    )
    (net (code "99") (name "M3.3V") (class "Default")
      (node (ref "C50") (pin "1") (pinfunction "1_1") (pintype "passive"))
      (node (ref "C56") (pin "1") (pinfunction "1_1") (pintype "passive"))
      (node (ref "C60") (pin "2") (pinfunction "2_2") (pintype "passive"))
      (node (ref "C61") (pin "2") (pinfunction "2_2") (pintype "passive"))
      (node (ref "J1") (pin "5") (pinfunction "5_5") (pintype "passive"))
      (node (ref "J1") (pin "7") (pinfunction "7_7") (pintype "passive"))
      (node (ref "J7") (pin "6") (pinfunction "6_6") (pintype "passive"))
      (node (ref "R80") (pin "2") (pinfunction "2_2") (pintype "passive"))
      (node (ref "R82") (pin "2") (pinfunction "2_2") (pintype "passive"))
      (node (ref "SW1") (pin "2") (pinfunction "2_2") (pintype "passive"))
      (node (ref "SW4") (pin "2") (pinfunction "2_2") (pintype "passive"))
      (node (ref "TP12") (pin "1") (pinfunction "1_1") (pintype "passive"))
      (node (ref "TP26") (pin "1") (pinfunction "1_1") (pintype "passive"))
      (node (ref "TP29") (pin "1") (pinfunction "1_1") (pintype "passive"))
      (node (ref "TP66") (pin "1") (pinfunction "1_1") (pintype "passive"))
    )
    (net (code "100") (name "Net-(C271-Pad1)") (class "Default")
      (node (ref "C271") (pin "1") (pinfunction "1_1") (pintype "passive"))
      (node (ref "R299") (pin "2") (pinfunction "2_2") (pintype "passive"))
      (node (ref "TP53") (pin "1") (pinfunction "1_1") (pintype "passive"))
    )
    (net (code "101") (name "Net-(D11-Pad2)") (class "Default")
      (node (ref "D11") (pin "2") (pinfunction "2_2") (pintype "passive"))
      (node (ref "J1") (pin "2") (pinfunction "2_2") (pintype "passive"))
      (node (ref "R93") (pin "1") (pinfunction "1_1") (pintype "passive"))
    )
    (net (code "102") (name "Net-(D12-Pad2)") (class "Default")
      (node (ref "D12") (pin "2") (pinfunction "2_2") (pintype "passive"))
      (node (ref "J1") (pin "3") (pinfunction "3_3") (pintype "passive"))
      (node (ref "R91") (pin "1") (pinfunction "1_1") (pintype "passive"))
    )
    (net (code "103") (name "Net-(D13-A)") (class "Default")
      (node (ref "D13") (pin "1") (pinfunction "A_1") (pintype "passive"))
      (node (ref "J3") (pin "1") (pinfunction "1_1") (pintype "passive"))
    )
    (net (code "104") (name "Net-(D16-K)") (class "Default")
      (node (ref "D16") (pin "2") (pinfunction "K_2") (pintype "passive"))
      (node (ref "J9") (pin "3") (pinfunction "3_3") (pintype "passive"))
      (node (ref "TP91") (pin "1") (pinfunction "1_1") (pintype "passive"))
    )
    (net (code "105") (name "Net-(J1-Pad6)") (class "Default")
      (node (ref "J1") (pin "6") (pinfunction "6_6") (pintype "passive"))
      (node (ref "R90") (pin "2") (pinfunction "2_2") (pintype "passive"))
    )
    (net (code "106") (name "Net-(J5-Pad1)") (class "Default")
      (node (ref "J5") (pin "1") (pinfunction "1_1") (pintype "passive"))
      (node (ref "J5") (pin "2") (pinfunction "2_2") (pintype "passive"))
      (node (ref "R290") (pin "2") (pinfunction "2_2") (pintype "passive"))
      (node (ref "R291") (pin "1") (pinfunction "1_1") (pintype "passive"))
    )
    (net (code "107") (name "Net-(J5-Pad5)") (class "Default")
      (node (ref "J5") (pin "5") (pinfunction "5_5") (pintype "passive"))
      (node (ref "R294") (pin "2") (pinfunction "2_2") (pintype "passive"))
    )
    (net (code "108") (name "Net-(J5-Pad7)") (class "Default")
      (node (ref "J5") (pin "7") (pinfunction "7_7") (pintype "passive"))
      (node (ref "R296") (pin "2") (pinfunction "2_2") (pintype "passive"))
    )
    (net (code "109") (name "Net-(J5-Pad8)") (class "Default")
      (node (ref "J5") (pin "8") (pinfunction "8_8") (pintype "passive"))
      (node (ref "R297") (pin "1") (pinfunction "1_1") (pintype "passive"))
    )
    (net (code "110") (name "Net-(J5-Pad9)") (class "Default")
      (node (ref "J5") (pin "9") (pinfunction "9_9") (pintype "passive"))
      (node (ref "R298") (pin "2") (pinfunction "2_2") (pintype "passive"))
    )
    (net (code "111") (name "Net-(J5-Pad10)") (class "Default")
      (node (ref "J5") (pin "10") (pinfunction "10_10") (pintype "passive"))
      (node (ref "R299") (pin "1") (pinfunction "1_1") (pintype "passive"))
    )
    (net (code "112") (name "Net-(J5-Pad11)") (class "Default")
      (node (ref "J5") (pin "11") (pinfunction "11_11") (pintype "passive"))
      (node (ref "R300") (pin "2") (pinfunction "2_2") (pintype "passive"))
    )
    (net (code "113") (name "Net-(J5-Pad12)") (class "Default")
      (node (ref "J5") (pin "12") (pinfunction "12_12") (pintype "passive"))
      (node (ref "R301") (pin "1") (pinfunction "1_1") (pintype "passive"))
    )
    (net (code "114") (name "Net-(J5-Pad13)") (class "Default")
      (node (ref "J5") (pin "13") (pinfunction "13_13") (pintype "passive"))
      (node (ref "R302") (pin "2") (pinfunction "2_2") (pintype "passive"))
    )
    (net (code "115") (name "Net-(J5-Pad14)") (class "Default")
      (node (ref "J5") (pin "14") (pinfunction "14_14") (pintype "passive"))
      (node (ref "R303") (pin "1") (pinfunction "1_1") (pintype "passive"))
    )
    (net (code "116") (name "Net-(J5-Pad15)") (class "Default")
      (node (ref "J5") (pin "15") (pinfunction "15_15") (pintype "passive"))
      (node (ref "R304") (pin "2") (pinfunction "2_2") (pintype "passive"))
    )
    (net (code "117") (name "Net-(J5-Pad16)") (class "Default")
      (node (ref "J5") (pin "16") (pinfunction "16_16") (pintype "passive"))
      (node (ref "R305") (pin "1") (pinfunction "1_1") (pintype "passive"))
    )
    (net (code "118") (name "Net-(J5-Pad17)") (class "Default")
      (node (ref "J5") (pin "17") (pinfunction "17_17") (pintype "passive"))
      (node (ref "R306") (pin "2") (pinfunction "2_2") (pintype "passive"))
    )
    (net (code "119") (name "Net-(J5-Pad18)") (class "Default")
      (node (ref "J5") (pin "18") (pinfunction "18_18") (pintype "passive"))
      (node (ref "R307") (pin "1") (pinfunction "1_1") (pintype "passive"))
    )
    (net (code "120") (name "Net-(J5-Pad19)") (class "Default")
      (node (ref "J5") (pin "19") (pinfunction "19_19") (pintype "passive"))
      (node (ref "J5") (pin "20") (pinfunction "20_20") (pintype "passive"))
      (node (ref "J5") (pin "23") (pinfunction "23_23") (pintype "passive"))
      (node (ref "J5") (pin "24") (pinfunction "24_24") (pintype "passive"))
      (node (ref "J5") (pin "27") (pinfunction "27_27") (pintype "passive"))
      (node (ref "J5") (pin "28") (pinfunction "28_28") (pintype "passive"))
      (node (ref "J5") (pin "3") (pinfunction "3_3") (pintype "passive"))
      (node (ref "J5") (pin "4") (pinfunction "4_4") (pintype "passive"))
      (node (ref "J5") (pin "6") (pinfunction "6_6") (pintype "passive"))
      (node (ref "R292") (pin "2") (pinfunction "2_2") (pintype "passive"))
      (node (ref "R293") (pin "1") (pinfunction "1_1") (pintype "passive"))
      (node (ref "R295") (pin "1") (pinfunction "1_1") (pintype "passive"))
      (node (ref "R308") (pin "2") (pinfunction "2_2") (pintype "passive"))
      (node (ref "R309") (pin "1") (pinfunction "1_1") (pintype "passive"))
    )
    (net (code "121") (name "Net-(J5-Pad21)") (class "Default")
      (node (ref "J5") (pin "21") (pinfunction "21_21") (pintype "passive"))
      (node (ref "R310") (pin "2") (pinfunction "2_2") (pintype "passive"))
    )
    (net (code "122") (name "Net-(J5-Pad22)") (class "Default")
      (node (ref "J5") (pin "22") (pinfunction "22_22") (pintype "passive"))
      (node (ref "R311") (pin "1") (pinfunction "1_1") (pintype "passive"))
    )
    (net (code "123") (name "Net-(J5-Pad25)") (class "Default")
      (node (ref "J5") (pin "25") (pinfunction "25_25") (pintype "passive"))
      (node (ref "R312") (pin "2") (pinfunction "2_2") (pintype "passive"))
    )
    (net (code "124") (name "Net-(J5-Pad26)") (class "Default")
      (node (ref "J5") (pin "26") (pinfunction "26_26") (pintype "passive"))
      (node (ref "R313") (pin "1") (pinfunction "1_1") (pintype "passive"))
    )
    (net (code "125") (name "Net-(J8-Pad2)") (class "Default")
      (node (ref "J8") (pin "2") (pinfunction "2_2") (pintype "passive"))
      (node (ref "R95") (pin "2") (pinfunction "2_2") (pintype "passive"))
    )
    (net (code "126") (name "Net-(J8-Pad5)") (class "Default")
      (node (ref "J8") (pin "5") (pinfunction "5_5") (pintype "passive"))
      (node (ref "R94") (pin "2") (pinfunction "2_2") (pintype "passive"))
    )
    (net (code "127") (name "Net-(LED1-Pad1)") (class "Default")
      (node (ref "LED1") (pin "1") (pinfunction "1_1") (pintype "passive"))
      (node (ref "R80") (pin "1") (pinfunction "1_1") (pintype "passive"))
    )
    (net (code "128") (name "Net-(LED1-Pad3)") (class "Default")
      (node (ref "LED1") (pin "3") (pinfunction "3_3") (pintype "passive"))
      (node (ref "R82") (pin "1") (pinfunction "1_1") (pintype "passive"))
    )
    (net (code "129") (name "Net-(R74-Pad2)") (class "Default")
      (node (ref "R74") (pin "2") (pinfunction "2_2") (pintype "passive"))
      (node (ref "VR1") (pin "2") (pinfunction "2_2") (pintype "passive"))
    )
    (net (code "130") (name "Net-(R75-Pad1)") (class "Default")
      (node (ref "R75") (pin "1") (pinfunction "1_1") (pintype "passive"))
      (node (ref "VR1") (pin "3") (pinfunction "3_3") (pintype "passive"))
    )
    (net (code "131") (name "Net-(R76-Pad2)") (class "Default")
      (node (ref "R76") (pin "2") (pinfunction "2_2") (pintype "passive"))
      (node (ref "VR2") (pin "2") (pinfunction "2_2") (pintype "passive"))
    )
    (net (code "132") (name "Net-(R77-Pad1)") (class "Default")
      (node (ref "R77") (pin "1") (pinfunction "1_1") (pintype "passive"))
      (node (ref "VR2") (pin "3") (pinfunction "3_3") (pintype "passive"))
    )
    (net (code "133") (name "Net-(R78-Pad2)") (class "Default")
      (node (ref "R78") (pin "2") (pinfunction "2_2") (pintype "passive"))
      (node (ref "VR3") (pin "2") (pinfunction "2_2") (pintype "passive"))
    )
    (net (code "134") (name "Net-(R79-Pad1)") (class "Default")
      (node (ref "R79") (pin "1") (pinfunction "1_1") (pintype "passive"))
      (node (ref "VR3") (pin "3") (pinfunction "3_3") (pintype "passive"))
    )
    (net (code "135") (name "Net-(R83-Pad2)") (class "Default")
      (node (ref "R83") (pin "2") (pinfunction "2_2") (pintype "passive"))
      (node (ref "VR4") (pin "2") (pinfunction "2_2") (pintype "passive"))
    )
    (net (code "136") (name "Net-(R84-Pad1)") (class "Default")
      (node (ref "R84") (pin "1") (pinfunction "1_1") (pintype "passive"))
      (node (ref "VR4") (pin "3") (pinfunction "3_3") (pintype "passive"))
    )
    (net (code "137") (name "Net-(R85-Pad2)") (class "Default")
      (node (ref "R85") (pin "2") (pinfunction "2_2") (pintype "passive"))
      (node (ref "VR5") (pin "2") (pinfunction "2_2") (pintype "passive"))
    )
    (net (code "138") (name "Net-(R86-Pad1)") (class "Default")
      (node (ref "R86") (pin "1") (pinfunction "1_1") (pintype "passive"))
      (node (ref "VR5") (pin "3") (pinfunction "3_3") (pintype "passive"))
    )
    (net (code "139") (name "Net-(R87-Pad2)") (class "Default")
      (node (ref "R87") (pin "2") (pinfunction "2_2") (pintype "passive"))
      (node (ref "VR6") (pin "2") (pinfunction "2_2") (pintype "passive"))
    )
    (net (code "140") (name "Net-(R88-Pad1)") (class "Default")
      (node (ref "R88") (pin "1") (pinfunction "1_1") (pintype "passive"))
      (node (ref "VR6") (pin "3") (pinfunction "3_3") (pintype "passive"))
    )
    (net (code "141") (name "Net-(R276-Pad2)") (class "Default")
      (node (ref "R276") (pin "2") (pinfunction "2_2") (pintype "passive"))
      (node (ref "SW1") (pin "3") (pinfunction "3_3") (pintype "passive"))
    )
    (net (code "142") (name "Net-(R277-Pad2)") (class "Default")
      (node (ref "R277") (pin "2") (pinfunction "2_2") (pintype "passive"))
      (node (ref "SW4") (pin "3") (pinfunction "3_3") (pintype "passive"))
    )
    (net (code "143") (name "Net-(SW1-Pad1)") (class "Default")
      (node (ref "SW1") (pin "1") (pinfunction "1_1") (pintype "passive"))
      (node (ref "TP5") (pin "1") (pinfunction "1_1") (pintype "passive"))
    )
    (net (code "144") (name "Net-(SW4-Pad1)") (class "Default")
      (node (ref "SW4") (pin "1") (pinfunction "1_1") (pintype "passive"))
      (node (ref "TP19") (pin "1") (pinfunction "1_1") (pintype "passive"))
    )
    (net (code "145") (name "S_+18V") (class "Default")
      (node (ref "R294") (pin "1") (pinfunction "1_1") (pintype "passive"))
      (node (ref "TP44") (pin "1") (pinfunction "1_1") (pintype "passive"))
    )
    (net (code "146") (name "unconnected-(D16-Pad3)") (class "Default")
      (node (ref "D16") (pin "3") (pinfunction "3_3") (pintype "passive"))
    )
    (net (code "147") (name "unconnected-(J3-Pad7)") (class "Default")
      (node (ref "J3") (pin "7") (pinfunction "7_7") (pintype "passive"))
    )
    (net (code "148") (name "unconnected-(J8-Pad6)") (class "Default")
      (node (ref "J8") (pin "6") (pinfunction "6_6") (pintype "passive"))
    )
    (net (code "149") (name "unconnected-(SW1-Pad4)") (class "Default")
      (node (ref "SW1") (pin "4") (pinfunction "4_4") (pintype "passive"))
    )
    (net (code "150") (name "unconnected-(SW2-Pad1)") (class "Default")
      (node (ref "SW2") (pin "1") (pinfunction "1_1") (pintype "passive"))
    )
    (net (code "151") (name "unconnected-(SW2-Pad8)") (class "Default")
      (node (ref "SW2") (pin "8") (pinfunction "8_8") (pintype "passive"))
    )
    (net (code "152") (name "unconnected-(SW2-Pad9)") (class "Default")
      (node (ref "SW2") (pin "9") (pinfunction "9_9") (pintype "passive"))
    )
    (net (code "153") (name "unconnected-(SW2-Pad10)") (class "Default")
      (node (ref "SW2") (pin "10") (pinfunction "10_10") (pintype "passive"))
    )
    (net (code "154") (name "unconnected-(SW3-Pad1)") (class "Default")
      (node (ref "SW3") (pin "1") (pinfunction "1_1") (pintype "passive"))
    )
    (net (code "155") (name "unconnected-(SW3-Pad8)") (class "Default")
      (node (ref "SW3") (pin "8") (pinfunction "8_8") (pintype "passive"))
    )
    (net (code "156") (name "unconnected-(SW3-Pad9)") (class "Default")
      (node (ref "SW3") (pin "9") (pinfunction "9_9") (pintype "passive"))
    )
    (net (code "157") (name "unconnected-(SW3-Pad10)") (class "Default")
      (node (ref "SW3") (pin "10") (pinfunction "10_10") (pintype "passive"))
    )
    (net (code "158") (name "unconnected-(SW4-Pad4)") (class "Default")
      (node (ref "SW4") (pin "4") (pinfunction "4_4") (pintype "passive"))
    )
  )
)
